# interfacez_r1.net
KiCad netlist of a schematic drawn in EAGLE
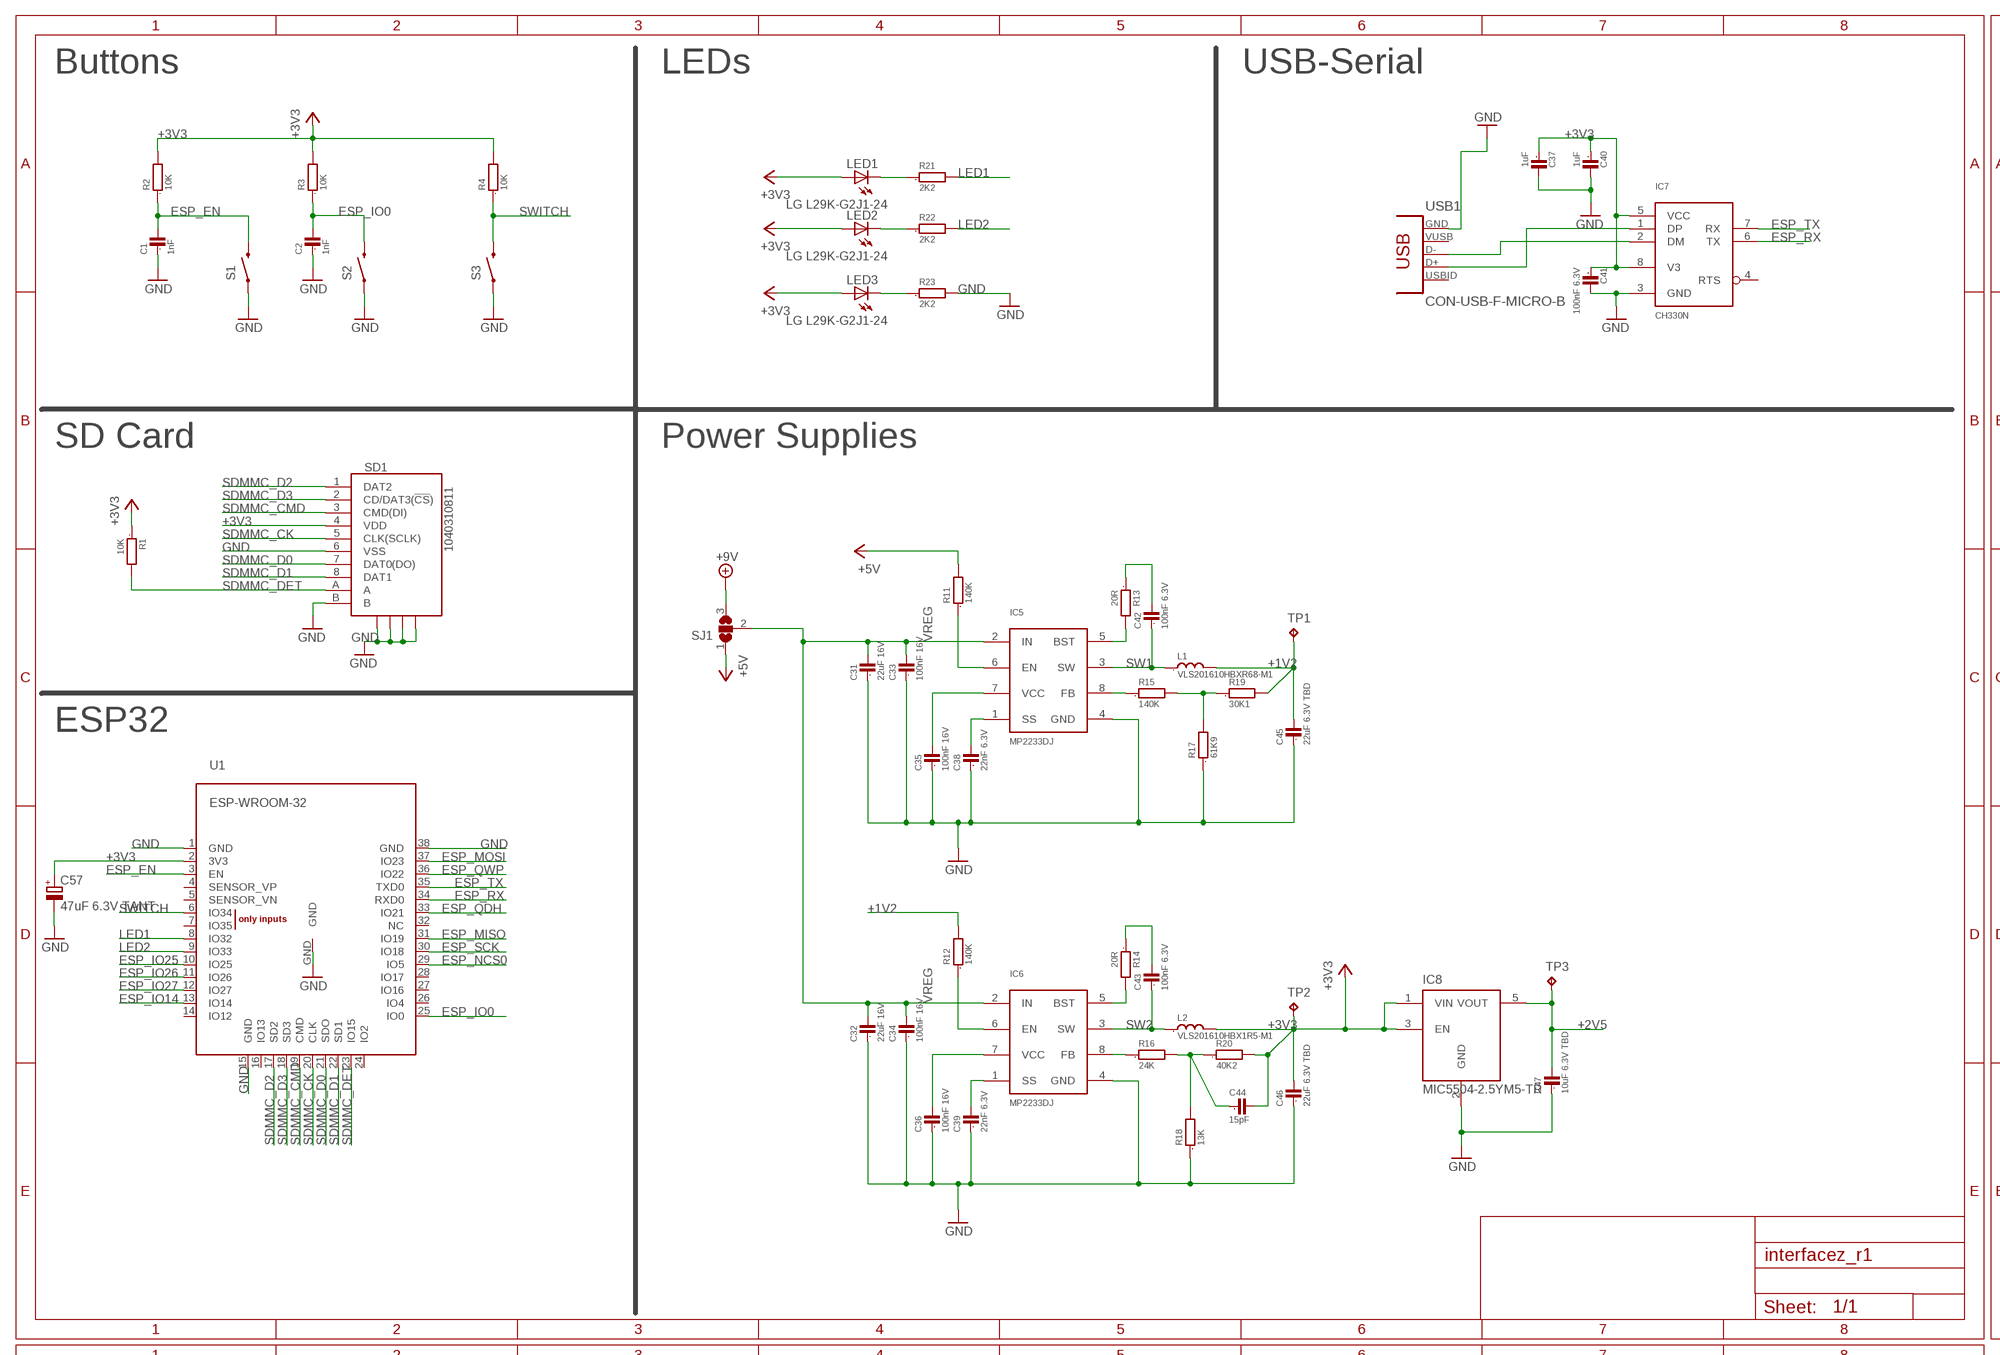
[diagram p0: schematic, sheet 1, part 1 of 3]
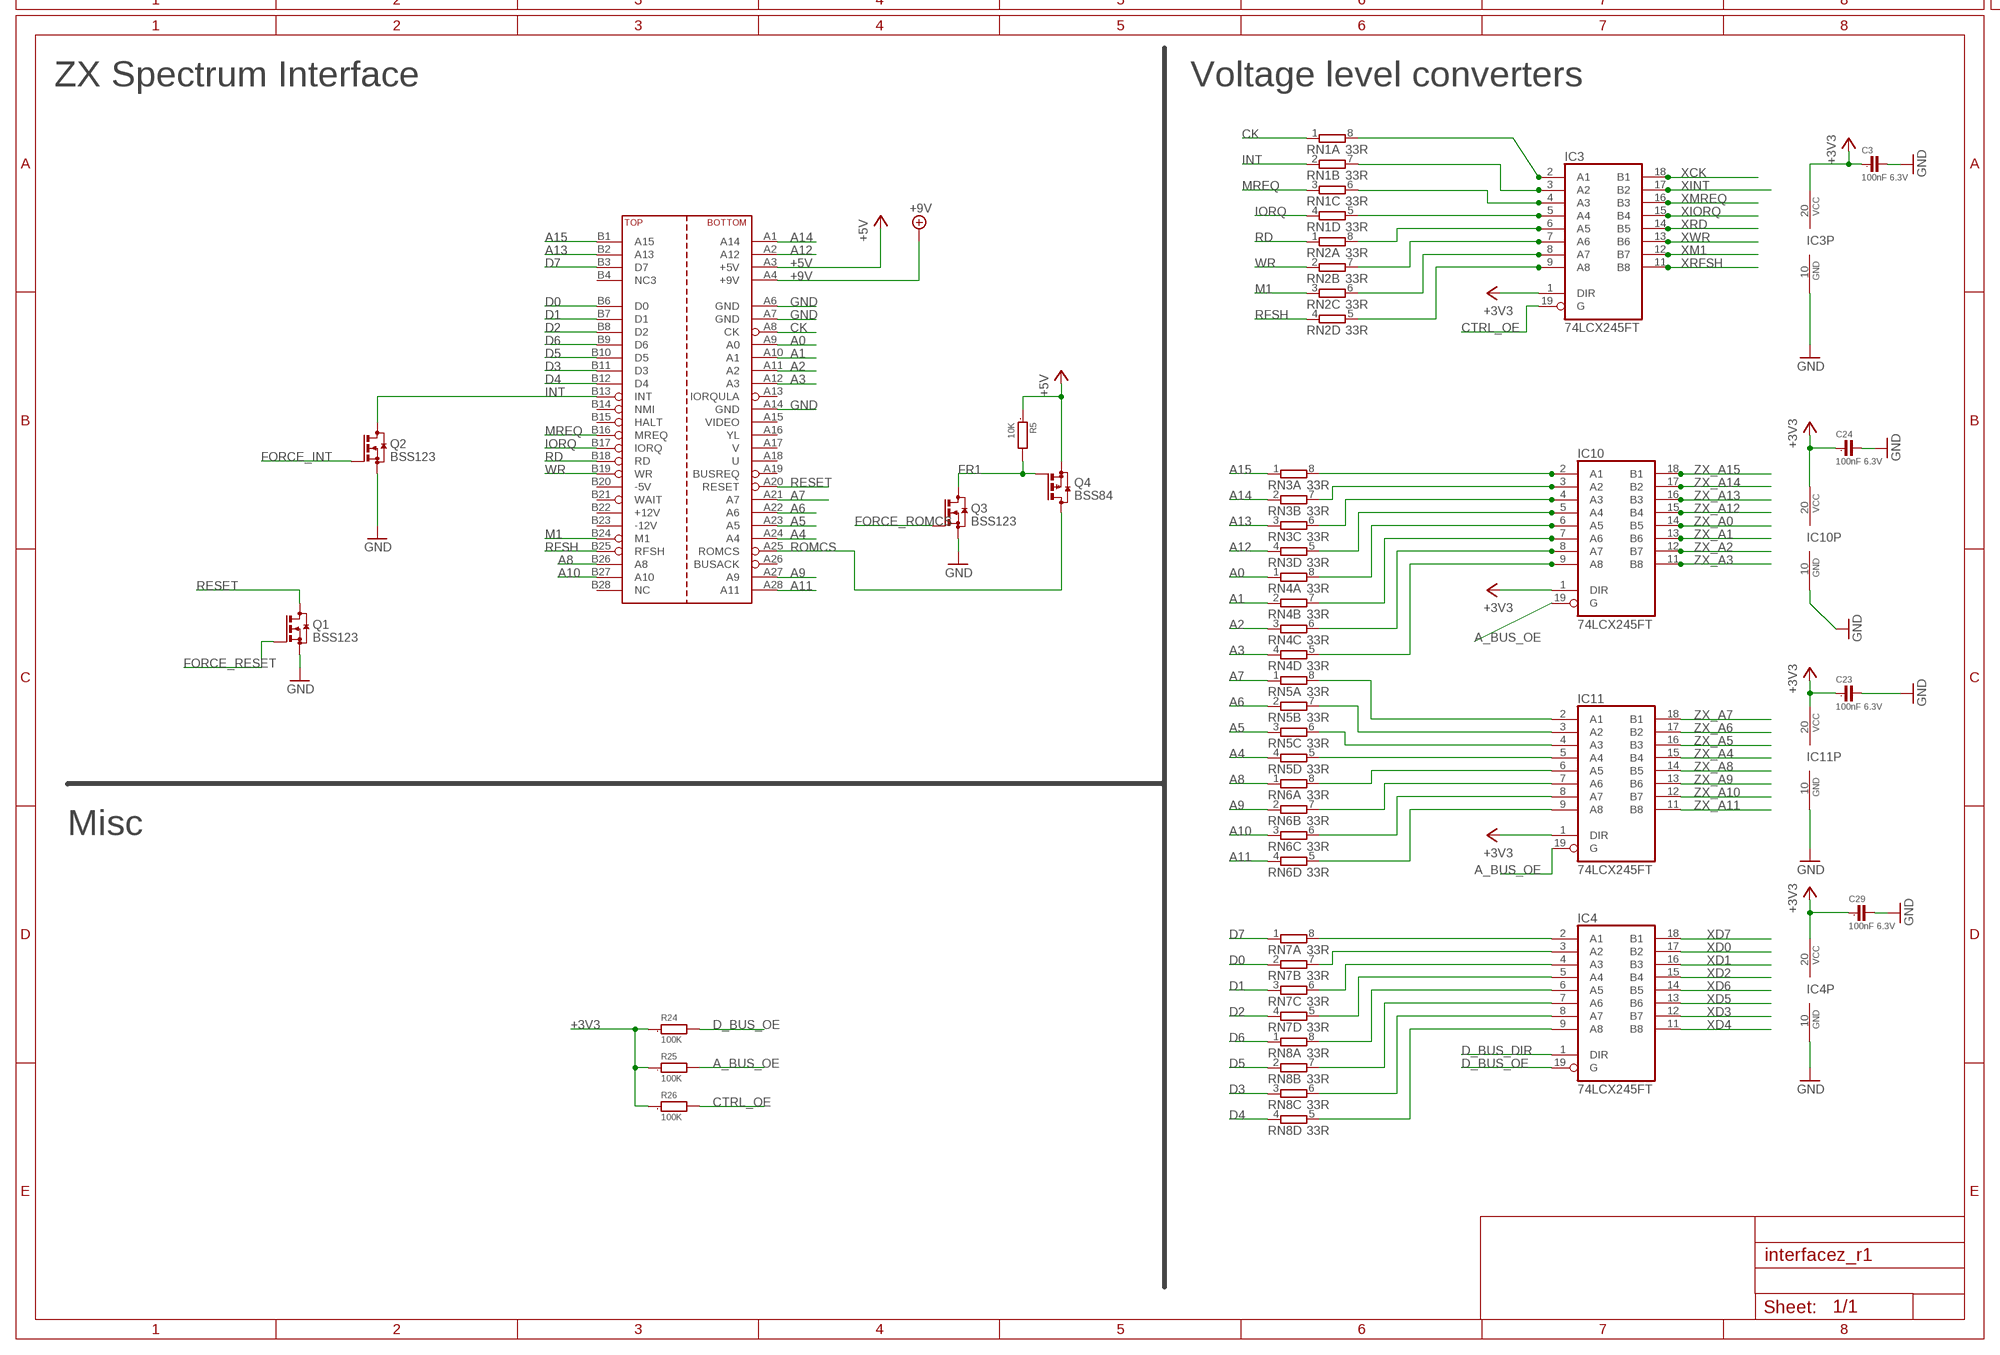
[diagram p1: schematic, sheet 1, part 2 of 3]
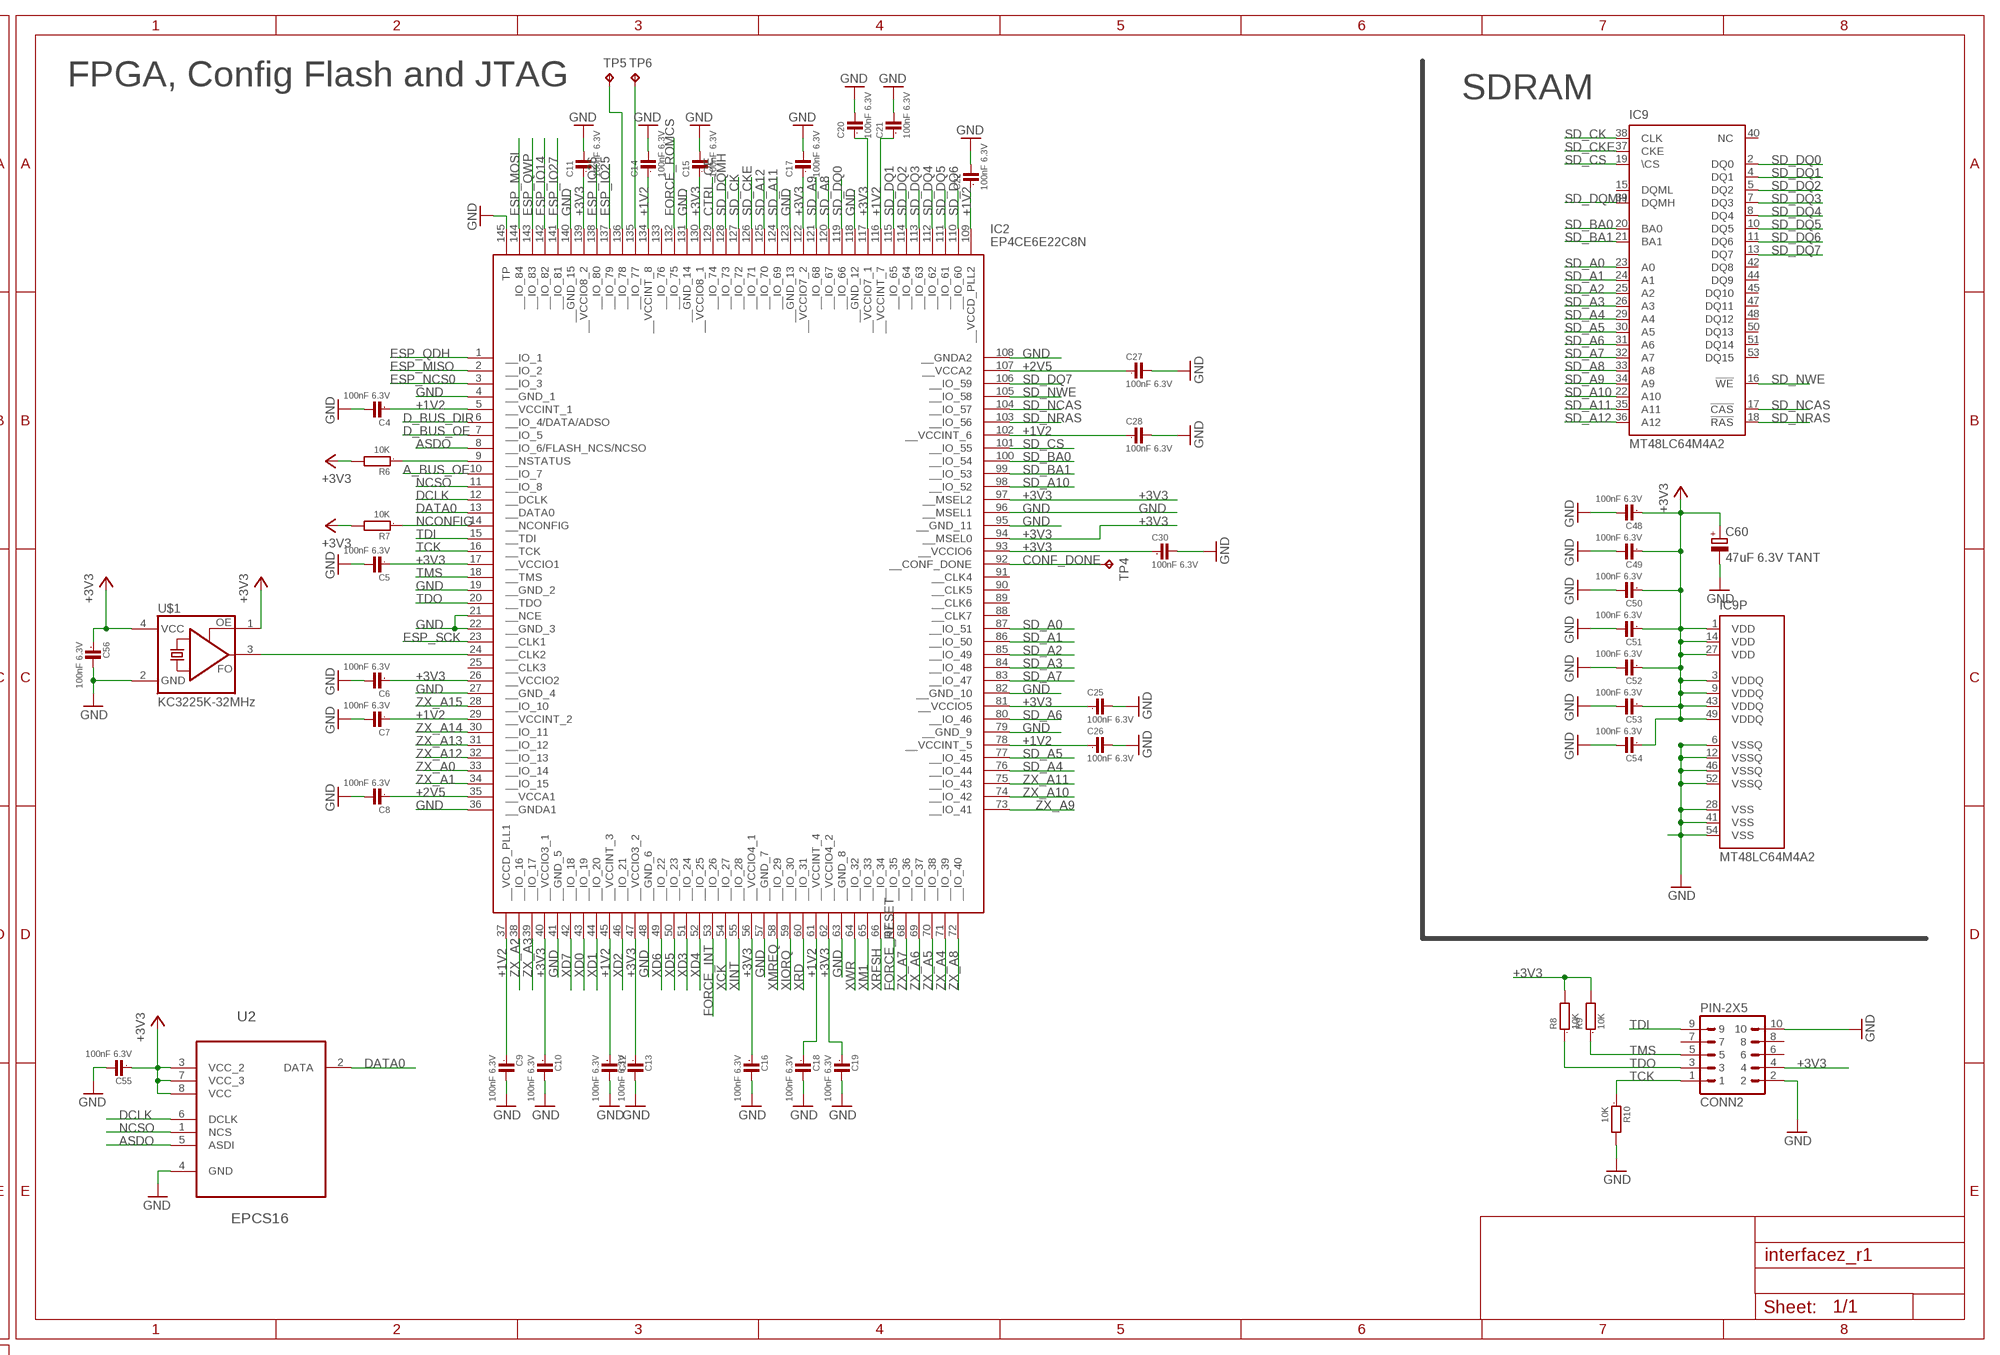
[diagram p2: schematic, sheet 1, part 3 of 3]

(export (version "E")
  (design (tool "Eeschema 10.0.6"))
  (components
    (comp (ref "C1")
      (value "1nF")
      (footprint "eagle-import:0603")
      (libsource (lib "eagle-import") (part "C0603"))
    )
    (comp (ref "C2")
      (value "1nF")
      (footprint "eagle-import:0603")
      (libsource (lib "eagle-import") (part "C0603"))
    )
    (comp (ref "C3")
      (value "100nF 6.3V")
      (footprint "eagle-import:0603")
      (libsource (lib "eagle-import") (part "C0603"))
    )
    (comp (ref "C4")
      (value "100nF 6.3V")
      (footprint "eagle-import:0603")
      (libsource (lib "eagle-import") (part "C0603"))
    )
    (comp (ref "C5")
      (value "100nF 6.3V")
      (footprint "eagle-import:0603")
      (libsource (lib "eagle-import") (part "C0603"))
    )
    (comp (ref "C6")
      (value "100nF 6.3V")
      (footprint "eagle-import:0603")
      (libsource (lib "eagle-import") (part "C0603"))
    )
    (comp (ref "C7")
      (value "100nF 6.3V")
      (footprint "eagle-import:0603")
      (libsource (lib "eagle-import") (part "C0603"))
    )
    (comp (ref "C8")
      (value "100nF 6.3V")
      (footprint "eagle-import:0603")
      (libsource (lib "eagle-import") (part "C0603"))
    )
    (comp (ref "C9")
      (value "100nF 6.3V")
      (footprint "eagle-import:0603")
      (libsource (lib "eagle-import") (part "C0603"))
    )
    (comp (ref "C10")
      (value "100nF 6.3V")
      (footprint "eagle-import:0603")
      (libsource (lib "eagle-import") (part "C0603"))
    )
    (comp (ref "C11")
      (value "100nF 6.3V")
      (footprint "eagle-import:0603")
      (libsource (lib "eagle-import") (part "C0603"))
    )
    (comp (ref "C12")
      (value "100nF 6.3V")
      (footprint "eagle-import:0603")
      (libsource (lib "eagle-import") (part "C0603"))
    )
    (comp (ref "C13")
      (value "100nF 6.3V")
      (footprint "eagle-import:0603")
      (libsource (lib "eagle-import") (part "C0603"))
    )
    (comp (ref "C14")
      (value "100nF 6.3V")
      (footprint "eagle-import:0603")
      (libsource (lib "eagle-import") (part "C0603"))
    )
    (comp (ref "C15")
      (value "100nF 6.3V")
      (footprint "eagle-import:0603")
      (libsource (lib "eagle-import") (part "C0603"))
    )
    (comp (ref "C16")
      (value "100nF 6.3V")
      (footprint "eagle-import:0603")
      (libsource (lib "eagle-import") (part "C0603"))
    )
    (comp (ref "C17")
      (value "100nF 6.3V")
      (footprint "eagle-import:0603")
      (libsource (lib "eagle-import") (part "C0603"))
    )
    (comp (ref "C18")
      (value "100nF 6.3V")
      (footprint "eagle-import:0603")
      (libsource (lib "eagle-import") (part "C0603"))
    )
    (comp (ref "C19")
      (value "100nF 6.3V")
      (footprint "eagle-import:0603")
      (libsource (lib "eagle-import") (part "C0603"))
    )
    (comp (ref "C20")
      (value "100nF 6.3V")
      (footprint "eagle-import:0603")
      (libsource (lib "eagle-import") (part "C0603"))
    )
    (comp (ref "C21")
      (value "100nF 6.3V")
      (footprint "eagle-import:0603")
      (libsource (lib "eagle-import") (part "C0603"))
    )
    (comp (ref "C22")
      (value "100nF 6.3V")
      (footprint "eagle-import:0603")
      (libsource (lib "eagle-import") (part "C0603"))
    )
    (comp (ref "C23")
      (value "100nF 6.3V")
      (footprint "eagle-import:0603")
      (libsource (lib "eagle-import") (part "C0603"))
    )
    (comp (ref "C24")
      (value "100nF 6.3V")
      (footprint "eagle-import:0603")
      (libsource (lib "eagle-import") (part "C0603"))
    )
    (comp (ref "C25")
      (value "100nF 6.3V")
      (footprint "eagle-import:0603")
      (libsource (lib "eagle-import") (part "C0603"))
    )
    (comp (ref "C26")
      (value "100nF 6.3V")
      (footprint "eagle-import:0603")
      (libsource (lib "eagle-import") (part "C0603"))
    )
    (comp (ref "C27")
      (value "100nF 6.3V")
      (footprint "eagle-import:0603")
      (libsource (lib "eagle-import") (part "C0603"))
    )
    (comp (ref "C28")
      (value "100nF 6.3V")
      (footprint "eagle-import:0603")
      (libsource (lib "eagle-import") (part "C0603"))
    )
    (comp (ref "C29")
      (value "100nF 6.3V")
      (footprint "eagle-import:0603")
      (libsource (lib "eagle-import") (part "C0603"))
    )
    (comp (ref "C30")
      (value "100nF 6.3V")
      (footprint "eagle-import:0603")
      (libsource (lib "eagle-import") (part "C0603"))
    )
    (comp (ref "C31")
      (value "22uF 16V")
      (footprint "eagle-import:1210")
      (libsource (lib "eagle-import") (part "C1210"))
    )
    (comp (ref "C32")
      (value "22uF 16V")
      (footprint "eagle-import:1210")
      (libsource (lib "eagle-import") (part "C1210"))
    )
    (comp (ref "C33")
      (value "100nF 16V")
      (footprint "eagle-import:0603")
      (libsource (lib "eagle-import") (part "C0603"))
    )
    (comp (ref "C34")
      (value "100nF 16V")
      (footprint "eagle-import:0603")
      (libsource (lib "eagle-import") (part "C0603"))
    )
    (comp (ref "C35")
      (value "100nF 16V")
      (footprint "eagle-import:0603")
      (libsource (lib "eagle-import") (part "C0603"))
    )
    (comp (ref "C36")
      (value "100nF 16V")
      (footprint "eagle-import:0603")
      (libsource (lib "eagle-import") (part "C0603"))
    )
    (comp (ref "C37")
      (value "1uF")
      (footprint "eagle-import:0603")
      (libsource (lib "eagle-import") (part "C0603"))
    )
    (comp (ref "C38")
      (value "22nF 6.3V")
      (footprint "eagle-import:0603")
      (libsource (lib "eagle-import") (part "C0603"))
    )
    (comp (ref "C39")
      (value "22nF 6.3V")
      (footprint "eagle-import:0603")
      (libsource (lib "eagle-import") (part "C0603"))
    )
    (comp (ref "C40")
      (value "1uF")
      (footprint "eagle-import:0603")
      (libsource (lib "eagle-import") (part "C0603"))
    )
    (comp (ref "C41")
      (value "100nF 6.3V")
      (footprint "eagle-import:0603")
      (libsource (lib "eagle-import") (part "C0603"))
    )
    (comp (ref "C42")
      (value "100nF 6.3V")
      (footprint "eagle-import:0603")
      (libsource (lib "eagle-import") (part "C0603"))
    )
    (comp (ref "C43")
      (value "100nF 6.3V")
      (footprint "eagle-import:0603")
      (libsource (lib "eagle-import") (part "C0603"))
    )
    (comp (ref "C44")
      (value "15pF")
      (footprint "eagle-import:0603")
      (libsource (lib "eagle-import") (part "C0603"))
    )
    (comp (ref "C45")
      (value "22uF 6.3V TBD")
      (footprint "eagle-import:0805")
      (libsource (lib "eagle-import") (part "C0805"))
    )
    (comp (ref "C46")
      (value "22uF 6.3V TBD")
      (footprint "eagle-import:0805")
      (libsource (lib "eagle-import") (part "C0805"))
    )
    (comp (ref "C47")
      (value "10uF 6.3V TBD")
      (footprint "eagle-import:0805")
      (libsource (lib "eagle-import") (part "C0805"))
    )
    (comp (ref "C48")
      (value "100nF 6.3V")
      (footprint "eagle-import:0603")
      (libsource (lib "eagle-import") (part "C0603"))
    )
    (comp (ref "C49")
      (value "100nF 6.3V")
      (footprint "eagle-import:0603")
      (libsource (lib "eagle-import") (part "C0603"))
    )
    (comp (ref "C50")
      (value "100nF 6.3V")
      (footprint "eagle-import:0603")
      (libsource (lib "eagle-import") (part "C0603"))
    )
    (comp (ref "C51")
      (value "100nF 6.3V")
      (footprint "eagle-import:0603")
      (libsource (lib "eagle-import") (part "C0603"))
    )
    (comp (ref "C52")
      (value "100nF 6.3V")
      (footprint "eagle-import:0603")
      (libsource (lib "eagle-import") (part "C0603"))
    )
    (comp (ref "C53")
      (value "100nF 6.3V")
      (footprint "eagle-import:0603")
      (libsource (lib "eagle-import") (part "C0603"))
    )
    (comp (ref "C54")
      (value "100nF 6.3V")
      (footprint "eagle-import:0603")
      (libsource (lib "eagle-import") (part "C0603"))
    )
    (comp (ref "C55")
      (value "100nF 6.3V")
      (footprint "eagle-import:0603")
      (libsource (lib "eagle-import") (part "C0603"))
    )
    (comp (ref "C56")
      (value "100nF 6.3V")
      (footprint "eagle-import:0603")
      (libsource (lib "eagle-import") (part "C0603"))
    )
    (comp (ref "C57")
      (value "47uF 6.3V TANT")
      (footprint "eagle-import:TANT_CASE_A")
      (libsource (lib "eagle-import") (part "TANT_CASE_A"))
    )
    (comp (ref "C60")
      (value "47uF 6.3V TANT")
      (footprint "eagle-import:TANT_CASE_A")
      (libsource (lib "eagle-import") (part "TANT_CASE_A"))
    )
    (comp (ref "CONN1")
      (value "ZX_EDGE_DAUGHTERBOARD")
      (footprint "eagle-import:ZX-EDGE-DAUGHTERBOARD")
      (libsource (lib "eagle-import") (part "ZX_EDGE_DAUGHTERBOARD"))
    )
    (comp (ref "CONN2")
      (value "PIN-2X5")
      (footprint "eagle-import:PIN-2X5")
      (libsource (lib "eagle-import") (part "PIN-2X5"))
    )
    (comp (ref "IC2")
      (value "EP4CE6E22C8N")
      (footprint "eagle-import:QFP50P2200X2200X165-145N")
      (fields (field (name "MOUSER_PART_NUMBER") "989-EP4CE6E22C8N"))
      (libsource (lib "eagle-import") (part "EP4CE6E22C8N"))
    )
    (comp (ref "IC3")
      (value "74LCX245FT")
      (footprint "eagle-import:TSSOP20")
      (libsource (lib "eagle-import") (part "74245"))
    )
    (comp (ref "IC4")
      (value "74LCX245FT")
      (footprint "eagle-import:TSSOP20")
      (libsource (lib "eagle-import") (part "74245"))
    )
    (comp (ref "IC5")
      (value "MP2233DJ")
      (footprint "eagle-import:SOT23-8L")
      (libsource (lib "eagle-import") (part "MP2233DJ"))
    )
    (comp (ref "IC6")
      (value "MP2233DJ")
      (footprint "eagle-import:SOT23-8L")
      (libsource (lib "eagle-import") (part "MP2233DJ"))
    )
    (comp (ref "IC7")
      (value "CH330N")
      (footprint "eagle-import:SOIC8")
      (libsource (lib "eagle-import") (part "CH330N"))
    )
    (comp (ref "IC8")
      (value "MIC5504-2.5YM5-TR")
      (footprint "eagle-import:SOT23-5L")
      (libsource (lib "eagle-import") (part "MIC550X"))
    )
    (comp (ref "IC9")
      (value "MT48LC64M4A2")
      (footprint "eagle-import:TSOP54-400")
      (libsource (lib "eagle-import") (part "MT48LC64M4A2"))
    )
    (comp (ref "IC10")
      (value "74LCX245FT")
      (footprint "eagle-import:TSSOP20")
      (libsource (lib "eagle-import") (part "74245"))
    )
    (comp (ref "IC11")
      (value "74LCX245FT")
      (footprint "eagle-import:TSSOP20")
      (libsource (lib "eagle-import") (part "74245"))
    )
    (comp (ref "L1")
      (value "VLS201610HBXR68-M1")
      (footprint "eagle-import:IND_0806")
      (libsource (lib "eagle-import") (part "VLS201610HBXR68-M1"))
    )
    (comp (ref "L2")
      (value "VLS201610HBX1R5-M1")
      (footprint "eagle-import:IND_0806")
      (libsource (lib "eagle-import") (part "VLS201610HBX1R5-M1"))
    )
    (comp (ref "LED1")
      (value "LG L29K-G2J1-24")
      (footprint "eagle-import:LED-603")
      (libsource (lib "eagle-import") (part "LED-0603"))
    )
    (comp (ref "LED2")
      (value "LG L29K-G2J1-24")
      (footprint "eagle-import:LED-603")
      (libsource (lib "eagle-import") (part "LED-0603"))
    )
    (comp (ref "LED3")
      (value "LG L29K-G2J1-24")
      (footprint "eagle-import:LED-603")
      (libsource (lib "eagle-import") (part "LED-0603"))
    )
    (comp (ref "Q1")
      (value "BSS123")
      (footprint "eagle-import:SOT23")
      (libsource (lib "eagle-import") (part "BSS123"))
    )
    (comp (ref "Q2")
      (value "BSS123")
      (footprint "eagle-import:SOT23")
      (libsource (lib "eagle-import") (part "BSS123"))
    )
    (comp (ref "Q3")
      (value "BSS123")
      (footprint "eagle-import:SOT23")
      (libsource (lib "eagle-import") (part "BSS123"))
    )
    (comp (ref "Q4")
      (value "BSS84")
      (footprint "eagle-import:SOT23")
      (libsource (lib "eagle-import") (part "BSS84"))
    )
    (comp (ref "R1")
      (value "10K")
      (footprint "eagle-import:0603")
      (libsource (lib "eagle-import") (part "R0603"))
    )
    (comp (ref "R2")
      (value "10K")
      (footprint "eagle-import:0603")
      (libsource (lib "eagle-import") (part "R0603"))
    )
    (comp (ref "R3")
      (value "10K")
      (footprint "eagle-import:0603")
      (libsource (lib "eagle-import") (part "R0603"))
    )
    (comp (ref "R4")
      (value "10K")
      (footprint "eagle-import:0603")
      (libsource (lib "eagle-import") (part "R0603"))
    )
    (comp (ref "R5")
      (value "10K")
      (footprint "eagle-import:0603")
      (libsource (lib "eagle-import") (part "R0603"))
    )
    (comp (ref "R6")
      (value "10K")
      (footprint "eagle-import:0603")
      (libsource (lib "eagle-import") (part "R0603"))
    )
    (comp (ref "R7")
      (value "10K")
      (footprint "eagle-import:0603")
      (libsource (lib "eagle-import") (part "R0603"))
    )
    (comp (ref "R8")
      (value "10K")
      (footprint "eagle-import:0603")
      (libsource (lib "eagle-import") (part "R0603"))
    )
    (comp (ref "R9")
      (value "10K")
      (footprint "eagle-import:0603")
      (libsource (lib "eagle-import") (part "R0603"))
    )
    (comp (ref "R10")
      (value "10K")
      (footprint "eagle-import:0603")
      (libsource (lib "eagle-import") (part "R0603"))
    )
    (comp (ref "R11")
      (value "140K")
      (footprint "eagle-import:0603")
      (libsource (lib "eagle-import") (part "R0603"))
    )
    (comp (ref "R12")
      (value "140K")
      (footprint "eagle-import:0603")
      (libsource (lib "eagle-import") (part "R0603"))
    )
    (comp (ref "R13")
      (value "20R")
      (footprint "eagle-import:0603")
      (libsource (lib "eagle-import") (part "R0603"))
    )
    (comp (ref "R14")
      (value "20R")
      (footprint "eagle-import:0603")
      (libsource (lib "eagle-import") (part "R0603"))
    )
    (comp (ref "R15")
      (value "140K")
      (footprint "eagle-import:0603")
      (libsource (lib "eagle-import") (part "R0603"))
    )
    (comp (ref "R16")
      (value "24K")
      (footprint "eagle-import:0603")
      (libsource (lib "eagle-import") (part "R0603"))
    )
    (comp (ref "R17")
      (value "61K9")
      (footprint "eagle-import:0603")
      (libsource (lib "eagle-import") (part "R0603"))
    )
    (comp (ref "R18")
      (value "13K")
      (footprint "eagle-import:0603")
      (libsource (lib "eagle-import") (part "R0603"))
    )
    (comp (ref "R19")
      (value "30K1")
      (footprint "eagle-import:0603")
      (libsource (lib "eagle-import") (part "R0603"))
    )
    (comp (ref "R20")
      (value "40K2")
      (footprint "eagle-import:0603")
      (libsource (lib "eagle-import") (part "R0603"))
    )
    (comp (ref "R21")
      (value "2K2")
      (footprint "eagle-import:0603")
      (libsource (lib "eagle-import") (part "R0603"))
    )
    (comp (ref "R22")
      (value "2K2")
      (footprint "eagle-import:0603")
      (libsource (lib "eagle-import") (part "R0603"))
    )
    (comp (ref "R23")
      (value "2K2")
      (footprint "eagle-import:0603")
      (libsource (lib "eagle-import") (part "R0603"))
    )
    (comp (ref "R24")
      (value "100K")
      (footprint "eagle-import:0603")
      (libsource (lib "eagle-import") (part "R0603"))
    )
    (comp (ref "R25")
      (value "100K")
      (footprint "eagle-import:0603")
      (libsource (lib "eagle-import") (part "R0603"))
    )
    (comp (ref "R26")
      (value "100K")
      (footprint "eagle-import:0603")
      (libsource (lib "eagle-import") (part "R0603"))
    )
    (comp (ref "RN1")
      (value "33R")
      (footprint "eagle-import:EXB28V")
      (libsource (lib "eagle-import") (part "4R-NEXB28V"))
    )
    (comp (ref "RN2")
      (value "33R")
      (footprint "eagle-import:EXB28V")
      (libsource (lib "eagle-import") (part "4R-NEXB28V"))
    )
    (comp (ref "RN3")
      (value "33R")
      (footprint "eagle-import:EXB28V")
      (libsource (lib "eagle-import") (part "4R-NEXB28V"))
    )
    (comp (ref "RN4")
      (value "33R")
      (footprint "eagle-import:EXB28V")
      (libsource (lib "eagle-import") (part "4R-NEXB28V"))
    )
    (comp (ref "RN5")
      (value "33R")
      (footprint "eagle-import:EXB28V")
      (libsource (lib "eagle-import") (part "4R-NEXB28V"))
    )
    (comp (ref "RN6")
      (value "33R")
      (footprint "eagle-import:EXB28V")
      (libsource (lib "eagle-import") (part "4R-NEXB28V"))
    )
    (comp (ref "RN7")
      (value "33R")
      (footprint "eagle-import:EXB28V")
      (libsource (lib "eagle-import") (part "4R-NEXB28V"))
    )
    (comp (ref "RN8")
      (value "33R")
      (footprint "eagle-import:EXB28V")
      (libsource (lib "eagle-import") (part "4R-NEXB28V"))
    )
    (comp (ref "S1")
      (value "SWITCHES_SMD-4")
      (footprint "eagle-import:TACTILE_SWITCH_TALL")
      (libsource (lib "eagle-import") (part "SWITCHES_SMD-4"))
    )
    (comp (ref "S2")
      (value "SWITCHES_SMD-4")
      (footprint "eagle-import:TACTILE_SWITCH_TALL")
      (libsource (lib "eagle-import") (part "SWITCHES_SMD-4"))
    )
    (comp (ref "S3")
      (value "SWITCHES_SMD-4")
      (footprint "eagle-import:TACTILE_SWITCH_TALL")
      (libsource (lib "eagle-import") (part "SWITCHES_SMD-4"))
    )
    (comp (ref "SD1")
      (value "1040310811")
      (footprint "eagle-import:1040310811")
      (libsource (lib "eagle-import") (part "1040310811"))
    )
    (comp (ref "SJ1")
      (value "SJ2W")
      (footprint "eagle-import:SJ_2")
      (libsource (lib "eagle-import") (part "SJ2W"))
    )
    (comp (ref "TP1")
      (value "TPTP12R")
      (footprint "eagle-import:TP12R")
      (libsource (lib "eagle-import") (part "TPTP12R"))
    )
    (comp (ref "TP2")
      (value "TPTP12R")
      (footprint "eagle-import:TP12R")
      (libsource (lib "eagle-import") (part "TPTP12R"))
    )
    (comp (ref "TP3")
      (value "TPTP12R")
      (footprint "eagle-import:TP12R")
      (libsource (lib "eagle-import") (part "TPTP12R"))
    )
    (comp (ref "TP4")
      (value "TPTP08R")
      (footprint "eagle-import:TP08R")
      (libsource (lib "eagle-import") (part "TPTP08R"))
    )
    (comp (ref "TP5")
      (value "TPTP12R")
      (footprint "eagle-import:TP12R")
      (libsource (lib "eagle-import") (part "TPTP12R"))
    )
    (comp (ref "TP6")
      (value "TPTP12R")
      (footprint "eagle-import:TP12R")
      (libsource (lib "eagle-import") (part "TPTP12R"))
    )
    (comp (ref "U$1")
      (value "KC3225K-32MHz")
      (footprint "eagle-import:KC3225K")
      (libsource (lib "eagle-import") (part "KC3225K"))
    )
    (comp (ref "U1")
      (value "ESP-WROOM-32")
      (footprint "eagle-import:ESP-WROOM-32")
      (libsource (lib "eagle-import") (part "ESP-WROOM-32"))
    )
    (comp (ref "U2")
      (value "EPCS16")
      (footprint "eagle-import:SOIC127P600X175-8N")
      (fields (field (name "MPN") "EPCS1SI8N"))
      (libsource (lib "eagle-import") (part "EPCS1SI8N"))
    )
    (comp (ref "USB1")
      (value "CON-USB-F-MICRO-B")
      (footprint "eagle-import:CONN_USB_MICRO-B")
      (libsource (lib "eagle-import") (part "CON-USB-F-MICRO-B"))
    )
  )
  (nets
    (net (code "1") (name "+3V3") (class "Default")
      (node (ref "C10") (pin "1") (pinfunction "1_1") (pintype "passive"))
      (node (ref "C11") (pin "1") (pinfunction "1_1") (pintype "passive"))
      (node (ref "C13") (pin "1") (pinfunction "1_1") (pintype "passive"))
      (node (ref "C15") (pin "1") (pinfunction "1_1") (pintype "passive"))
      (node (ref "C16") (pin "1") (pinfunction "1_1") (pintype "passive"))
      (node (ref "C17") (pin "1") (pinfunction "1_1") (pintype "passive"))
      (node (ref "C19") (pin "1") (pinfunction "1_1") (pintype "passive"))
      (node (ref "C20") (pin "1") (pinfunction "1_1") (pintype "passive"))
      (node (ref "C23") (pin "1") (pinfunction "1_1") (pintype "passive"))
      (node (ref "C24") (pin "1") (pinfunction "1_1") (pintype "passive"))
      (node (ref "C25") (pin "1") (pinfunction "1_1") (pintype "passive"))
      (node (ref "C29") (pin "1") (pinfunction "1_1") (pintype "passive"))
      (node (ref "C3") (pin "1") (pinfunction "1_1") (pintype "passive"))
      (node (ref "C30") (pin "1") (pinfunction "1_1") (pintype "passive"))
      (node (ref "C37") (pin "1") (pinfunction "1_1") (pintype "passive"))
      (node (ref "C40") (pin "1") (pinfunction "1_1") (pintype "passive"))
      (node (ref "C41") (pin "1") (pinfunction "1_1") (pintype "passive"))
      (node (ref "C44") (pin "2") (pinfunction "2_2") (pintype "passive"))
      (node (ref "C46") (pin "2") (pinfunction "2_2") (pintype "passive"))
      (node (ref "C48") (pin "1") (pinfunction "1_1") (pintype "passive"))
      (node (ref "C49") (pin "1") (pinfunction "1_1") (pintype "passive"))
      (node (ref "C5") (pin "1") (pinfunction "1_1") (pintype "passive"))
      (node (ref "C50") (pin "1") (pinfunction "1_1") (pintype "passive"))
      (node (ref "C51") (pin "1") (pinfunction "1_1") (pintype "passive"))
      (node (ref "C52") (pin "1") (pinfunction "1_1") (pintype "passive"))
      (node (ref "C53") (pin "1") (pinfunction "1_1") (pintype "passive"))
      (node (ref "C54") (pin "1") (pinfunction "1_1") (pintype "passive"))
      (node (ref "C55") (pin "1") (pinfunction "1_1") (pintype "passive"))
      (node (ref "C56") (pin "1") (pinfunction "1_1") (pintype "passive"))
      (node (ref "C57") (pin "PLUS") (pinfunction "+_PLUS") (pintype "passive"))
      (node (ref "C6") (pin "1") (pinfunction "1_1") (pintype "passive"))
      (node (ref "C60") (pin "PLUS") (pinfunction "+_PLUS") (pintype "passive"))
      (node (ref "CONN2") (pin "4") (pinfunction "4_4") (pintype "passive"))
      (node (ref "IC10") (pin "1") (pinfunction "DIR_1") (pintype "input"))
      (node (ref "IC10") (pin "20") (pinfunction "VCC_20") (pintype "power_in"))
      (node (ref "IC11") (pin "1") (pinfunction "DIR_1") (pintype "input"))
      (node (ref "IC11") (pin "20") (pinfunction "VCC_20") (pintype "power_in"))
      (node (ref "IC2") (pin "117") (pinfunction "__VCCIO7_1_117") (pintype "power_in"))
      (node (ref "IC2") (pin "122") (pinfunction "__VCCIO7_2_122") (pintype "power_in"))
      (node (ref "IC2") (pin "130") (pinfunction "__VCCIO8_1_130") (pintype "power_in"))
      (node (ref "IC2") (pin "139") (pinfunction "__VCCIO8_2_139") (pintype "power_in"))
      (node (ref "IC2") (pin "17") (pinfunction "__VCCIO1_17") (pintype "power_in"))
      (node (ref "IC2") (pin "26") (pinfunction "__VCCIO2_26") (pintype "power_in"))
      (node (ref "IC2") (pin "40") (pinfunction "__VCCIO3_1_40") (pintype "power_in"))
      (node (ref "IC2") (pin "47") (pinfunction "__VCCIO3_2_47") (pintype "power_in"))
      (node (ref "IC2") (pin "56") (pinfunction "__VCCIO4_1_56") (pintype "power_in"))
      (node (ref "IC2") (pin "62") (pinfunction "__VCCIO4_2_62") (pintype "power_in"))
      (node (ref "IC2") (pin "81") (pinfunction "__VCCIO5_81") (pintype "power_in"))
      (node (ref "IC2") (pin "93") (pinfunction "__VCCIO6_93") (pintype "power_in"))
      (node (ref "IC2") (pin "94") (pinfunction "__MSEL0_94") (pintype "bidirectional"))
      (node (ref "IC2") (pin "97") (pinfunction "__MSEL2_97") (pintype "bidirectional"))
      (node (ref "IC3") (pin "1") (pinfunction "DIR_1") (pintype "input"))
      (node (ref "IC3") (pin "20") (pinfunction "VCC_20") (pintype "power_in"))
      (node (ref "IC4") (pin "20") (pinfunction "VCC_20") (pintype "power_in"))
      (node (ref "IC7") (pin "5") (pinfunction "VCC_5") (pintype "power_in"))
      (node (ref "IC7") (pin "8") (pinfunction "V3_8") (pintype "passive"))
      (node (ref "IC8") (pin "1") (pinfunction "VIN_1") (pintype "power_in"))
      (node (ref "IC8") (pin "3") (pinfunction "EN_3") (pintype "input"))
      (node (ref "IC9") (pin "1") (pinfunction "VDD_1") (pintype "power_in"))
      (node (ref "IC9") (pin "14") (pinfunction "VDD_14") (pintype "power_in"))
      (node (ref "IC9") (pin "27") (pinfunction "VDD_27") (pintype "power_in"))
      (node (ref "IC9") (pin "3") (pinfunction "VDDQ_3") (pintype "power_in"))
      (node (ref "IC9") (pin "43") (pinfunction "VDDQ_43") (pintype "power_in"))
      (node (ref "IC9") (pin "49") (pinfunction "VDDQ_49") (pintype "power_in"))
      (node (ref "IC9") (pin "9") (pinfunction "VDDQ_9") (pintype "power_in"))
      (node (ref "L2") (pin "P$2") (pinfunction "2_P$2") (pintype "passive"))
      (node (ref "LED1") (pin "A") (pinfunction "A_A") (pintype "passive"))
      (node (ref "LED2") (pin "A") (pinfunction "A_A") (pintype "passive"))
      (node (ref "LED3") (pin "A") (pinfunction "A_A") (pintype "passive"))
      (node (ref "R1") (pin "1") (pinfunction "1_1") (pintype "passive"))
      (node (ref "R2") (pin "2") (pinfunction "2_2") (pintype "passive"))
      (node (ref "R20") (pin "2") (pinfunction "2_2") (pintype "passive"))
      (node (ref "R24") (pin "1") (pinfunction "1_1") (pintype "passive"))
      (node (ref "R25") (pin "1") (pinfunction "1_1") (pintype "passive"))
      (node (ref "R26") (pin "1") (pinfunction "1_1") (pintype "passive"))
      (node (ref "R3") (pin "2") (pinfunction "2_2") (pintype "passive"))
      (node (ref "R4") (pin "2") (pinfunction "2_2") (pintype "passive"))
      (node (ref "R6") (pin "2") (pinfunction "2_2") (pintype "passive"))
      (node (ref "R7") (pin "2") (pinfunction "2_2") (pintype "passive"))
      (node (ref "R8") (pin "2") (pinfunction "2_2") (pintype "passive"))
      (node (ref "R9") (pin "2") (pinfunction "2_2") (pintype "passive"))
      (node (ref "SD1") (pin "4") (pinfunction "VDD_4") (pintype "power_in"))
      (node (ref "TP2") (pin "TP") (pinfunction "TP_TP") (pintype "input"))
      (node (ref "U$1") (pin "1") (pinfunction "OE_1") (pintype "input"))
      (node (ref "U$1") (pin "4") (pinfunction "VCC_4") (pintype "power_in"))
      (node (ref "U1") (pin "2") (pinfunction "3V3_2") (pintype "bidirectional"))
      (node (ref "U2") (pin "3") (pinfunction "VCC_2_3") (pintype "power_in"))
      (node (ref "U2") (pin "7") (pinfunction "VCC_3_7") (pintype "power_in"))
      (node (ref "U2") (pin "8") (pinfunction "VCC_8") (pintype "power_in"))
    )
    (net (code "2") (name "+5V") (class "Default")
      (node (ref "CONN1") (pin "A3") (pinfunction "+5V_A3") (pintype "power_in"))
      (node (ref "Q4") (pin "2") (pinfunction "S_2") (pintype "passive"))
      (node (ref "R11") (pin "2") (pinfunction "2_2") (pintype "passive"))
      (node (ref "R5") (pin "1") (pinfunction "1_1") (pintype "passive"))
      (node (ref "SJ1") (pin "1") (pinfunction "1_1") (pintype "passive"))
    )
    (net (code "3") (name "+9V") (class "Default")
      (node (ref "CONN1") (pin "A4") (pinfunction "+9V_A4") (pintype "power_in"))
      (node (ref "SJ1") (pin "3") (pinfunction "3_3") (pintype "passive"))
    )
    (net (code "4") (name "/+1V2") (class "Default")
      (node (ref "C12") (pin "1") (pinfunction "1_1") (pintype "passive"))
      (node (ref "C14") (pin "1") (pinfunction "1_1") (pintype "passive"))
      (node (ref "C18") (pin "1") (pinfunction "1_1") (pintype "passive"))
      (node (ref "C21") (pin "1") (pinfunction "1_1") (pintype "passive"))
      (node (ref "C22") (pin "1") (pinfunction "1_1") (pintype "passive"))
      (node (ref "C26") (pin "1") (pinfunction "1_1") (pintype "passive"))
      (node (ref "C28") (pin "1") (pinfunction "1_1") (pintype "passive"))
      (node (ref "C4") (pin "1") (pinfunction "1_1") (pintype "passive"))
      (node (ref "C45") (pin "2") (pinfunction "2_2") (pintype "passive"))
      (node (ref "C7") (pin "1") (pinfunction "1_1") (pintype "passive"))
      (node (ref "C9") (pin "1") (pinfunction "1_1") (pintype "passive"))
      (node (ref "IC2") (pin "102") (pinfunction "__VCCINT_6_102") (pintype "power_in"))
      (node (ref "IC2") (pin "109") (pinfunction "__VCCD_PLL2_109") (pintype "power_in"))
      (node (ref "IC2") (pin "116") (pinfunction "__VCCINT_7_116") (pintype "power_in"))
      (node (ref "IC2") (pin "134") (pinfunction "__VCCINT_8_134") (pintype "power_in"))
      (node (ref "IC2") (pin "29") (pinfunction "__VCCINT_2_29") (pintype "power_in"))
      (node (ref "IC2") (pin "37") (pinfunction "__VCCD_PLL1_37") (pintype "power_in"))
      (node (ref "IC2") (pin "45") (pinfunction "__VCCINT_3_45") (pintype "power_in"))
      (node (ref "IC2") (pin "5") (pinfunction "__VCCINT_1_5") (pintype "power_in"))
      (node (ref "IC2") (pin "61") (pinfunction "__VCCINT_4_61") (pintype "power_in"))
      (node (ref "IC2") (pin "78") (pinfunction "__VCCINT_5_78") (pintype "power_in"))
      (node (ref "L1") (pin "P$2") (pinfunction "2_P$2") (pintype "passive"))
      (node (ref "R12") (pin "2") (pinfunction "2_2") (pintype "passive"))
      (node (ref "R19") (pin "2") (pinfunction "2_2") (pintype "passive"))
      (node (ref "TP1") (pin "TP") (pinfunction "TP_TP") (pintype "input"))
    )
    (net (code "5") (name "/+2V5") (class "Default")
      (node (ref "C27") (pin "1") (pinfunction "1_1") (pintype "passive"))
      (node (ref "C47") (pin "2") (pinfunction "2_2") (pintype "passive"))
      (node (ref "C8") (pin "1") (pinfunction "1_1") (pintype "passive"))
      (node (ref "IC2") (pin "107") (pinfunction "__VCCA2_107") (pintype "power_in"))
      (node (ref "IC2") (pin "35") (pinfunction "__VCCA1_35") (pintype "power_in"))
      (node (ref "IC8") (pin "5") (pinfunction "VOUT_5") (pintype "power_in"))
      (node (ref "TP3") (pin "TP") (pinfunction "TP_TP") (pintype "input"))
    )
    (net (code "6") (name "/+12V") (class "Default")
      (node (ref "CONN1") (pin "B22") (pinfunction "+12V_B22") (pintype "power_in"))
    )
    (net (code "7") (name "/-5V") (class "Default")
      (node (ref "CONN1") (pin "B20") (pinfunction "-5V_B20") (pintype "power_in"))
    )
    (net (code "8") (name "/-12V") (class "Default")
      (node (ref "CONN1") (pin "B23") (pinfunction "-12V_B23") (pintype "power_in"))
    )
    (net (code "9") (name "/A0") (class "Default")
      (node (ref "CONN1") (pin "A9") (pinfunction "A0_A9") (pintype "bidirectional"))
      (node (ref "RN4") (pin "1") (pinfunction "1_1") (pintype "passive"))
    )
    (net (code "10") (name "/A1") (class "Default")
      (node (ref "CONN1") (pin "A10") (pinfunction "A1_A10") (pintype "bidirectional"))
      (node (ref "RN4") (pin "2") (pinfunction "1_2") (pintype "passive"))
    )
    (net (code "11") (name "/A2") (class "Default")
      (node (ref "CONN1") (pin "A11") (pinfunction "A2_A11") (pintype "bidirectional"))
      (node (ref "RN4") (pin "3") (pinfunction "1_3") (pintype "passive"))
    )
    (net (code "12") (name "/A3") (class "Default")
      (node (ref "CONN1") (pin "A12") (pinfunction "A3_A12") (pintype "bidirectional"))
      (node (ref "RN4") (pin "4") (pinfunction "1_4") (pintype "passive"))
    )
    (net (code "13") (name "/A4") (class "Default")
      (node (ref "CONN1") (pin "A24") (pinfunction "A4_A24") (pintype "bidirectional"))
      (node (ref "RN5") (pin "4") (pinfunction "1_4") (pintype "passive"))
    )
    (net (code "14") (name "/A5") (class "Default")
      (node (ref "CONN1") (pin "A23") (pinfunction "A5_A23") (pintype "bidirectional"))
      (node (ref "RN5") (pin "3") (pinfunction "1_3") (pintype "passive"))
    )
    (net (code "15") (name "/A6") (class "Default")
      (node (ref "CONN1") (pin "A22") (pinfunction "A6_A22") (pintype "bidirectional"))
      (node (ref "RN5") (pin "2") (pinfunction "1_2") (pintype "passive"))
    )
    (net (code "16") (name "/A7") (class "Default")
      (node (ref "CONN1") (pin "A21") (pinfunction "A7_A21") (pintype "bidirectional"))
      (node (ref "RN5") (pin "1") (pinfunction "1_1") (pintype "passive"))
    )
    (net (code "17") (name "/A8") (class "Default")
      (node (ref "CONN1") (pin "B26") (pinfunction "A8_B26") (pintype "bidirectional"))
      (node (ref "RN6") (pin "1") (pinfunction "1_1") (pintype "passive"))
    )
    (net (code "18") (name "/A9") (class "Default")
      (node (ref "CONN1") (pin "A27") (pinfunction "A9_A27") (pintype "bidirectional"))
      (node (ref "RN6") (pin "2") (pinfunction "1_2") (pintype "passive"))
    )
    (net (code "19") (name "/A10") (class "Default")
      (node (ref "CONN1") (pin "B27") (pinfunction "A10_B27") (pintype "bidirectional"))
      (node (ref "RN6") (pin "3") (pinfunction "1_3") (pintype "passive"))
    )
    (net (code "20") (name "/A11") (class "Default")
      (node (ref "CONN1") (pin "A28") (pinfunction "A11_A28") (pintype "bidirectional"))
      (node (ref "RN6") (pin "4") (pinfunction "1_4") (pintype "passive"))
    )
    (net (code "21") (name "/A12") (class "Default")
      (node (ref "CONN1") (pin "A2") (pinfunction "A12_A2") (pintype "bidirectional"))
      (node (ref "RN3") (pin "4") (pinfunction "1_4") (pintype "passive"))
    )
    (net (code "22") (name "/A13") (class "Default")
      (node (ref "CONN1") (pin "B2") (pinfunction "A13_B2") (pintype "bidirectional"))
      (node (ref "RN3") (pin "3") (pinfunction "1_3") (pintype "passive"))
    )
    (net (code "23") (name "/A14") (class "Default")
      (node (ref "CONN1") (pin "A1") (pinfunction "A14_A1") (pintype "bidirectional"))
      (node (ref "RN3") (pin "2") (pinfunction "1_2") (pintype "passive"))
    )
    (net (code "24") (name "/A15") (class "Default")
      (node (ref "CONN1") (pin "B1") (pinfunction "A15_B1") (pintype "bidirectional"))
      (node (ref "RN3") (pin "1") (pinfunction "1_1") (pintype "passive"))
    )
    (net (code "25") (name "/ASDO") (class "Default")
      (node (ref "IC2") (pin "8") (pinfunction "__IO_6/FLASH_NCS/NCSO_8") (pintype "bidirectional"))
      (node (ref "U2") (pin "5") (pinfunction "ASDI_5") (pintype "input"))
    )
    (net (code "26") (name "/A_BUS_OE") (class "Default")
      (node (ref "IC10") (pin "19") (pinfunction "G_19") (pintype "input"))
      (node (ref "IC11") (pin "19") (pinfunction "G_19") (pintype "input"))
      (node (ref "IC2") (pin "10") (pinfunction "__IO_7_10") (pintype "bidirectional"))
      (node (ref "R25") (pin "2") (pinfunction "2_2") (pintype "passive"))
    )
    (net (code "27") (name "/CK") (class "Default")
      (node (ref "CONN1") (pin "A8") (pinfunction "CK_A8") (pintype "bidirectional"))
      (node (ref "RN1") (pin "1") (pinfunction "1_1") (pintype "passive"))
    )
    (net (code "28") (name "/CONF_DONE") (class "Default")
      (node (ref "IC2") (pin "92") (pinfunction "__CONF_DONE_92") (pintype "bidirectional"))
      (node (ref "TP4") (pin "TP") (pinfunction "TP_TP") (pintype "input"))
    )
    (net (code "29") (name "/CTRL_OE") (class "Default")
      (node (ref "IC2") (pin "129") (pinfunction "__IO_74_129") (pintype "bidirectional"))
      (node (ref "IC3") (pin "19") (pinfunction "G_19") (pintype "input"))
      (node (ref "R26") (pin "2") (pinfunction "2_2") (pintype "passive"))
    )
    (net (code "30") (name "/D0") (class "Default")
      (node (ref "CONN1") (pin "B6") (pinfunction "D0_B6") (pintype "bidirectional"))
      (node (ref "RN7") (pin "2") (pinfunction "1_2") (pintype "passive"))
    )
    (net (code "31") (name "/D1") (class "Default")
      (node (ref "CONN1") (pin "B7") (pinfunction "D1_B7") (pintype "bidirectional"))
      (node (ref "RN7") (pin "3") (pinfunction "1_3") (pintype "passive"))
    )
    (net (code "32") (name "/D2") (class "Default")
      (node (ref "CONN1") (pin "B8") (pinfunction "D2_B8") (pintype "bidirectional"))
      (node (ref "RN7") (pin "4") (pinfunction "1_4") (pintype "passive"))
    )
    (net (code "33") (name "/D3") (class "Default")
      (node (ref "CONN1") (pin "B11") (pinfunction "D3_B11") (pintype "bidirectional"))
      (node (ref "RN8") (pin "3") (pinfunction "1_3") (pintype "passive"))
    )
    (net (code "34") (name "/D4") (class "Default")
      (node (ref "CONN1") (pin "B12") (pinfunction "D4_B12") (pintype "bidirectional"))
      (node (ref "RN8") (pin "4") (pinfunction "1_4") (pintype "passive"))
    )
    (net (code "35") (name "/D5") (class "Default")
      (node (ref "CONN1") (pin "B10") (pinfunction "D5_B10") (pintype "bidirectional"))
      (node (ref "RN8") (pin "2") (pinfunction "1_2") (pintype "passive"))
    )
    (net (code "36") (name "/D6") (class "Default")
      (node (ref "CONN1") (pin "B9") (pinfunction "D6_B9") (pintype "bidirectional"))
      (node (ref "RN8") (pin "1") (pinfunction "1_1") (pintype "passive"))
    )
    (net (code "37") (name "/D7") (class "Default")
      (node (ref "CONN1") (pin "B3") (pinfunction "D7_B3") (pintype "bidirectional"))
      (node (ref "RN7") (pin "1") (pinfunction "1_1") (pintype "passive"))
    )
    (net (code "38") (name "/DATA0") (class "Default")
      (node (ref "IC2") (pin "13") (pinfunction "__DATA0_13") (pintype "bidirectional"))
      (node (ref "U2") (pin "2") (pinfunction "DATA_2") (pintype "output"))
    )
    (net (code "39") (name "/DCLK") (class "Default")
      (node (ref "IC2") (pin "12") (pinfunction "__DCLK_12") (pintype "input"))
      (node (ref "U2") (pin "6") (pinfunction "DCLK_6") (pintype "input"))
    )
    (net (code "40") (name "/D_BUS_DIR") (class "Default")
      (node (ref "IC2") (pin "6") (pinfunction "__IO_4/DATA/ADSO_6") (pintype "bidirectional"))
      (node (ref "IC4") (pin "1") (pinfunction "DIR_1") (pintype "input"))
    )
    (net (code "41") (name "/D_BUS_OE") (class "Default")
      (node (ref "IC2") (pin "7") (pinfunction "__IO_5_7") (pintype "bidirectional"))
      (node (ref "IC4") (pin "19") (pinfunction "G_19") (pintype "input"))
      (node (ref "R24") (pin "2") (pinfunction "2_2") (pintype "passive"))
    )
    (net (code "42") (name "/ESP_EN") (class "Default")
      (node (ref "C1") (pin "2") (pinfunction "2_2") (pintype "passive"))
      (node (ref "R2") (pin "1") (pinfunction "1_1") (pintype "passive"))
      (node (ref "S1") (pin "B2") (pinfunction "2_B2") (pintype "passive"))
      (node (ref "U1") (pin "3") (pinfunction "EN_3") (pintype "bidirectional"))
    )
    (net (code "43") (name "/ESP_IO0") (class "Default")
      (node (ref "C2") (pin "2") (pinfunction "2_2") (pintype "passive"))
      (node (ref "R3") (pin "1") (pinfunction "1_1") (pintype "passive"))
      (node (ref "S2") (pin "B2") (pinfunction "2_B2") (pintype "passive"))
      (node (ref "U1") (pin "25") (pinfunction "IO0_25") (pintype "bidirectional"))
    )
    (net (code "44") (name "/ESP_IO14") (class "Default")
      (node (ref "IC2") (pin "142") (pinfunction "__IO_82_142") (pintype "bidirectional"))
      (node (ref "U1") (pin "13") (pinfunction "IO14_13") (pintype "bidirectional"))
    )
    (net (code "45") (name "/ESP_IO25") (class "Default")
      (node (ref "IC2") (pin "137") (pinfunction "__IO_79_137") (pintype "bidirectional"))
      (node (ref "U1") (pin "10") (pinfunction "IO25_10") (pintype "bidirectional"))
    )
    (net (code "46") (name "/ESP_IO26") (class "Default")
      (node (ref "IC2") (pin "138") (pinfunction "__IO_80_138") (pintype "bidirectional"))
      (node (ref "U1") (pin "11") (pinfunction "IO26_11") (pintype "bidirectional"))
    )
    (net (code "47") (name "/ESP_IO27") (class "Default")
      (node (ref "IC2") (pin "141") (pinfunction "__IO_81_141") (pintype "bidirectional"))
      (node (ref "U1") (pin "12") (pinfunction "IO27_12") (pintype "bidirectional"))
    )
    (net (code "48") (name "/ESP_MISO") (class "Default")
      (node (ref "IC2") (pin "2") (pinfunction "__IO_2_2") (pintype "bidirectional"))
      (node (ref "U1") (pin "31") (pinfunction "IO19_31") (pintype "bidirectional"))
    )
    (net (code "49") (name "/ESP_MOSI") (class "Default")
      (node (ref "IC2") (pin "144") (pinfunction "__IO_84_144") (pintype "bidirectional"))
      (node (ref "U1") (pin "37") (pinfunction "IO23_37") (pintype "bidirectional"))
    )
    (net (code "50") (name "/ESP_NCS0") (class "Default")
      (node (ref "IC2") (pin "3") (pinfunction "__IO_3_3") (pintype "bidirectional"))
      (node (ref "U1") (pin "29") (pinfunction "IO5_29") (pintype "bidirectional"))
    )
    (net (code "51") (name "/ESP_QDH") (class "Default")
      (node (ref "IC2") (pin "1") (pinfunction "__IO_1_1") (pintype "bidirectional"))
      (node (ref "U1") (pin "33") (pinfunction "IO21_33") (pintype "bidirectional"))
    )
    (net (code "52") (name "/ESP_QWP") (class "Default")
      (node (ref "IC2") (pin "143") (pinfunction "__IO_83_143") (pintype "bidirectional"))
      (node (ref "U1") (pin "36") (pinfunction "IO22_36") (pintype "bidirectional"))
    )
    (net (code "53") (name "/ESP_RX") (class "Default")
      (node (ref "IC7") (pin "6") (pinfunction "TX_6") (pintype "output"))
      (node (ref "U1") (pin "34") (pinfunction "RXD0_34") (pintype "bidirectional"))
    )
    (net (code "54") (name "/ESP_SCK") (class "Default")
      (node (ref "IC2") (pin "23") (pinfunction "__CLK1_23") (pintype "input"))
      (node (ref "U1") (pin "30") (pinfunction "IO18_30") (pintype "bidirectional"))
    )
    (net (code "55") (name "/ESP_TX") (class "Default")
      (node (ref "IC7") (pin "7") (pinfunction "RX_7") (pintype "input"))
      (node (ref "U1") (pin "35") (pinfunction "TXD0_35") (pintype "bidirectional"))
    )
    (net (code "56") (name "/FORCE_INT") (class "Default")
      (node (ref "IC2") (pin "53") (pinfunction "__IO_26_53") (pintype "bidirectional"))
      (node (ref "Q2") (pin "1") (pinfunction "G_1") (pintype "passive"))
    )
    (net (code "57") (name "/FORCE_RESET") (class "Default")
      (node (ref "IC2") (pin "67") (pinfunction "__IO_35_67") (pintype "bidirectional"))
      (node (ref "Q1") (pin "1") (pinfunction "G_1") (pintype "passive"))
    )
    (net (code "58") (name "/FORCE_ROMCS") (class "Default")
      (node (ref "IC2") (pin "132") (pinfunction "__IO_75_132") (pintype "bidirectional"))
      (node (ref "Q3") (pin "1") (pinfunction "G_1") (pintype "passive"))
    )
    (net (code "59") (name "/FR1") (class "Default")
      (node (ref "Q3") (pin "3") (pinfunction "D_3") (pintype "passive"))
      (node (ref "Q4") (pin "1") (pinfunction "G_1") (pintype "passive"))
      (node (ref "R5") (pin "2") (pinfunction "2_2") (pintype "passive"))
    )
    (net (code "60") (name "/INT") (class "Default")
      (node (ref "CONN1") (pin "B13") (pinfunction "INT_B13") (pintype "bidirectional"))
      (node (ref "Q2") (pin "3") (pinfunction "D_3") (pintype "passive"))
      (node (ref "RN1") (pin "2") (pinfunction "1_2") (pintype "passive"))
    )
    (net (code "61") (name "/IORQ") (class "Default")
      (node (ref "CONN1") (pin "B17") (pinfunction "IORQ_B17") (pintype "bidirectional"))
      (node (ref "RN1") (pin "4") (pinfunction "1_4") (pintype "passive"))
    )
    (net (code "62") (name "/LED1") (class "Default")
      (node (ref "R21") (pin "2") (pinfunction "2_2") (pintype "passive"))
      (node (ref "U1") (pin "8") (pinfunction "IO32_8") (pintype "bidirectional"))
    )
    (net (code "63") (name "/LED2") (class "Default")
      (node (ref "R22") (pin "2") (pinfunction "2_2") (pintype "passive"))
      (node (ref "U1") (pin "9") (pinfunction "IO33_9") (pintype "bidirectional"))
    )
    (net (code "64") (name "/M1") (class "Default")
      (node (ref "CONN1") (pin "B24") (pinfunction "M1_B24") (pintype "bidirectional"))
      (node (ref "RN2") (pin "3") (pinfunction "1_3") (pintype "passive"))
    )
    (net (code "65") (name "/MREQ") (class "Default")
      (node (ref "CONN1") (pin "B16") (pinfunction "MREQ_B16") (pintype "bidirectional"))
      (node (ref "RN1") (pin "3") (pinfunction "1_3") (pintype "passive"))
    )
    (net (code "66") (name "/NCONFIG") (class "Default")
      (node (ref "IC2") (pin "14") (pinfunction "__NCONFIG_14") (pintype "bidirectional"))
      (node (ref "R7") (pin "1") (pinfunction "1_1") (pintype "passive"))
    )
    (net (code "67") (name "/NCSO") (class "Default")
      (node (ref "IC2") (pin "11") (pinfunction "__IO_8_11") (pintype "bidirectional"))
      (node (ref "U2") (pin "1") (pinfunction "NCS_1") (pintype "input"))
    )
    (net (code "68") (name "/RD") (class "Default")
      (node (ref "CONN1") (pin "B18") (pinfunction "RD_B18") (pintype "bidirectional"))
      (node (ref "RN2") (pin "1") (pinfunction "1_1") (pintype "passive"))
    )
    (net (code "69") (name "/RESET") (class "Default")
      (node (ref "CONN1") (pin "A20") (pinfunction "RESET_A20") (pintype "bidirectional"))
      (node (ref "Q1") (pin "3") (pinfunction "D_3") (pintype "passive"))
    )
    (net (code "70") (name "/RFSH") (class "Default")
      (node (ref "CONN1") (pin "B25") (pinfunction "RFSH_B25") (pintype "bidirectional"))
      (node (ref "RN2") (pin "4") (pinfunction "1_4") (pintype "passive"))
    )
    (net (code "71") (name "/ROMCS") (class "Default")
      (node (ref "CONN1") (pin "A25") (pinfunction "ROMCS_A25") (pintype "bidirectional"))
      (node (ref "Q4") (pin "3") (pinfunction "D_3") (pintype "passive"))
    )
    (net (code "72") (name "/SDMMC_CK") (class "Default")
      (node (ref "SD1") (pin "5") (pinfunction "CLK(SCLK)_5") (pintype "input"))
      (node (ref "U1") (pin "20") (pinfunction "CLK_20") (pintype "bidirectional"))
    )
    (net (code "73") (name "/SDMMC_CMD") (class "Default")
      (node (ref "SD1") (pin "3") (pinfunction "CMD(DI)_3") (pintype "bidirectional"))
      (node (ref "U1") (pin "19") (pinfunction "CMD_19") (pintype "bidirectional"))
    )
    (net (code "74") (name "/SDMMC_D0") (class "Default")
      (node (ref "SD1") (pin "7") (pinfunction "DAT0(DO)_7") (pintype "bidirectional"))
      (node (ref "U1") (pin "21") (pinfunction "SDO_21") (pintype "bidirectional"))
    )
    (net (code "75") (name "/SDMMC_D1") (class "Default")
      (node (ref "SD1") (pin "8") (pinfunction "DAT1_8") (pintype "bidirectional"))
      (node (ref "U1") (pin "22") (pinfunction "SD1_22") (pintype "bidirectional"))
    )
    (net (code "76") (name "/SDMMC_D2") (class "Default")
      (node (ref "SD1") (pin "1") (pinfunction "DAT2_1") (pintype "bidirectional"))
      (node (ref "U1") (pin "17") (pinfunction "SD2_17") (pintype "bidirectional"))
    )
    (net (code "77") (name "/SDMMC_D3") (class "Default")
      (node (ref "SD1") (pin "2") (pinfunction "CD/DAT3(~{CS})_2") (pintype "bidirectional"))
      (node (ref "U1") (pin "18") (pinfunction "SD3_18") (pintype "bidirectional"))
    )
    (net (code "78") (name "/SDMMC_DET") (class "Default")
      (node (ref "R1") (pin "2") (pinfunction "2_2") (pintype "passive"))
      (node (ref "SD1") (pin "A") (pinfunction "A_A") (pintype "passive"))
      (node (ref "U1") (pin "23") (pinfunction "IO15_23") (pintype "bidirectional"))
    )
    (net (code "79") (name "/SD_A0") (class "Default")
      (node (ref "IC2") (pin "87") (pinfunction "__IO_51_87") (pintype "bidirectional"))
      (node (ref "IC9") (pin "23") (pinfunction "A0_23") (pintype "input"))
    )
    (net (code "80") (name "/SD_A1") (class "Default")
      (node (ref "IC2") (pin "86") (pinfunction "__IO_50_86") (pintype "bidirectional"))
      (node (ref "IC9") (pin "24") (pinfunction "A1_24") (pintype "input"))
    )
    (net (code "81") (name "/SD_A2") (class "Default")
      (node (ref "IC2") (pin "85") (pinfunction "__IO_49_85") (pintype "bidirectional"))
      (node (ref "IC9") (pin "25") (pinfunction "A2_25") (pintype "input"))
    )
    (net (code "82") (name "/SD_A3") (class "Default")
      (node (ref "IC2") (pin "84") (pinfunction "__IO_48_84") (pintype "bidirectional"))
      (node (ref "IC9") (pin "26") (pinfunction "A3_26") (pintype "input"))
    )
    (net (code "83") (name "/SD_A4") (class "Default")
      (node (ref "IC2") (pin "76") (pinfunction "__IO_44_76") (pintype "bidirectional"))
      (node (ref "IC9") (pin "29") (pinfunction "A4_29") (pintype "input"))
    )
    (net (code "84") (name "/SD_A5") (class "Default")
      (node (ref "IC2") (pin "77") (pinfunction "__IO_45_77") (pintype "bidirectional"))
      (node (ref "IC9") (pin "30") (pinfunction "A5_30") (pintype "input"))
    )
    (net (code "85") (name "/SD_A6") (class "Default")
      (node (ref "IC2") (pin "80") (pinfunction "__IO_46_80") (pintype "bidirectional"))
      (node (ref "IC9") (pin "31") (pinfunction "A6_31") (pintype "input"))
    )
    (net (code "86") (name "/SD_A7") (class "Default")
      (node (ref "IC2") (pin "83") (pinfunction "__IO_47_83") (pintype "bidirectional"))
      (node (ref "IC9") (pin "32") (pinfunction "A7_32") (pintype "input"))
    )
    (net (code "87") (name "/SD_A8") (class "Default")
      (node (ref "IC2") (pin "120") (pinfunction "__IO_67_120") (pintype "bidirectional"))
      (node (ref "IC9") (pin "33") (pinfunction "A8_33") (pintype "input"))
    )
    (net (code "88") (name "/SD_A9") (class "Default")
      (node (ref "IC2") (pin "121") (pinfunction "__IO_68_121") (pintype "bidirectional"))
      (node (ref "IC9") (pin "34") (pinfunction "A9_34") (pintype "input"))
    )
    (net (code "89") (name "/SD_A10") (class "Default")
      (node (ref "IC2") (pin "98") (pinfunction "__IO_52_98") (pintype "bidirectional"))
      (node (ref "IC9") (pin "22") (pinfunction "A10_22") (pintype "input"))
    )
    (net (code "90") (name "/SD_A11") (class "Default")
      (node (ref "IC2") (pin "124") (pinfunction "__IO_69_124") (pintype "bidirectional"))
      (node (ref "IC9") (pin "35") (pinfunction "A11_35") (pintype "input"))
    )
    (net (code "91") (name "/SD_A12") (class "Default")
      (node (ref "IC2") (pin "125") (pinfunction "__IO_70_125") (pintype "bidirectional"))
      (node (ref "IC9") (pin "36") (pinfunction "A12_36") (pintype "input"))
    )
    (net (code "92") (name "/SD_BA0") (class "Default")
      (node (ref "IC2") (pin "100") (pinfunction "__IO_54_100") (pintype "bidirectional"))
      (node (ref "IC9") (pin "20") (pinfunction "BA0_20") (pintype "input"))
    )
    (net (code "93") (name "/SD_BA1") (class "Default")
      (node (ref "IC2") (pin "99") (pinfunction "__IO_53_99") (pintype "bidirectional"))
      (node (ref "IC9") (pin "21") (pinfunction "BA1_21") (pintype "input"))
    )
    (net (code "94") (name "/SD_CK") (class "Default")
      (node (ref "IC2") (pin "127") (pinfunction "__IO_72_127") (pintype "bidirectional"))
      (node (ref "IC9") (pin "38") (pinfunction "CLK_38") (pintype "input"))
    )
    (net (code "95") (name "/SD_CKE") (class "Default")
      (node (ref "IC2") (pin "126") (pinfunction "__IO_71_126") (pintype "bidirectional"))
      (node (ref "IC9") (pin "37") (pinfunction "CKE_37") (pintype "input"))
    )
    (net (code "96") (name "/SD_CS") (class "Default")
      (node (ref "IC2") (pin "101") (pinfunction "__IO_55_101") (pintype "bidirectional"))
      (node (ref "IC9") (pin "19") (pinfunction "\\CS_19") (pintype "input"))
    )
    (net (code "97") (name "/SD_DQ0") (class "Default")
      (node (ref "IC2") (pin "119") (pinfunction "__IO_66_119") (pintype "bidirectional"))
      (node (ref "IC9") (pin "2") (pinfunction "DQ0_2") (pintype "tri_state"))
    )
    (net (code "98") (name "/SD_DQ1") (class "Default")
      (node (ref "IC2") (pin "115") (pinfunction "__IO_65_115") (pintype "bidirectional"))
      (node (ref "IC9") (pin "4") (pinfunction "DQ1_4") (pintype "tri_state"))
    )
    (net (code "99") (name "/SD_DQ2") (class "Default")
      (node (ref "IC2") (pin "114") (pinfunction "__IO_64_114") (pintype "bidirectional"))
      (node (ref "IC9") (pin "5") (pinfunction "DQ2_5") (pintype "tri_state"))
    )
    (net (code "100") (name "/SD_DQ3") (class "Default")
      (node (ref "IC2") (pin "113") (pinfunction "__IO_63_113") (pintype "bidirectional"))
      (node (ref "IC9") (pin "7") (pinfunction "DQ3_7") (pintype "tri_state"))
    )
    (net (code "101") (name "/SD_DQ4") (class "Default")
      (node (ref "IC2") (pin "112") (pinfunction "__IO_62_112") (pintype "bidirectional"))
      (node (ref "IC9") (pin "8") (pinfunction "DQ4_8") (pintype "tri_state"))
    )
    (net (code "102") (name "/SD_DQ5") (class "Default")
      (node (ref "IC2") (pin "111") (pinfunction "__IO_61_111") (pintype "bidirectional"))
      (node (ref "IC9") (pin "10") (pinfunction "DQ5_10") (pintype "tri_state"))
    )
    (net (code "103") (name "/SD_DQ6") (class "Default")
      (node (ref "IC2") (pin "110") (pinfunction "__IO_60_110") (pintype "bidirectional"))
      (node (ref "IC9") (pin "11") (pinfunction "DQ6_11") (pintype "tri_state"))
    )
    (net (code "104") (name "/SD_DQ7") (class "Default")
      (node (ref "IC2") (pin "106") (pinfunction "__IO_59_106") (pintype "bidirectional"))
      (node (ref "IC9") (pin "13") (pinfunction "DQ7_13") (pintype "tri_state"))
    )
    (net (code "105") (name "/SD_DQMH") (class "Default")
      (node (ref "IC2") (pin "128") (pinfunction "__IO_73_128") (pintype "bidirectional"))
      (node (ref "IC9") (pin "39") (pinfunction "DQMH_39") (pintype "input"))
    )
    (net (code "106") (name "/SD_NCAS") (class "Default")
      (node (ref "IC2") (pin "104") (pinfunction "__IO_57_104") (pintype "bidirectional"))
      (node (ref "IC9") (pin "17") (pinfunction "~{CAS}_17") (pintype "input"))
    )
    (net (code "107") (name "/SD_NRAS") (class "Default")
      (node (ref "IC2") (pin "103") (pinfunction "__IO_56_103") (pintype "bidirectional"))
      (node (ref "IC9") (pin "18") (pinfunction "~{RAS}_18") (pintype "input"))
    )
    (net (code "108") (name "/SD_NWE") (class "Default")
      (node (ref "IC2") (pin "105") (pinfunction "__IO_58_105") (pintype "bidirectional"))
      (node (ref "IC9") (pin "16") (pinfunction "~{WE}_16") (pintype "input"))
    )
    (net (code "109") (name "/SW1") (class "Default")
      (node (ref "C42") (pin "1") (pinfunction "1_1") (pintype "passive"))
      (node (ref "IC5") (pin "3") (pinfunction "SW_3") (pintype "passive"))
      (node (ref "L1") (pin "P$1") (pinfunction "1_P$1") (pintype "passive"))
    )
    (net (code "110") (name "/SW2") (class "Default")
      (node (ref "C43") (pin "1") (pinfunction "1_1") (pintype "passive"))
      (node (ref "IC6") (pin "3") (pinfunction "SW_3") (pintype "passive"))
      (node (ref "L2") (pin "P$1") (pinfunction "1_P$1") (pintype "passive"))
    )
    (net (code "111") (name "/SWITCH") (class "Default")
      (node (ref "R4") (pin "1") (pinfunction "1_1") (pintype "passive"))
      (node (ref "S3") (pin "B2") (pinfunction "2_B2") (pintype "passive"))
      (node (ref "U1") (pin "6") (pinfunction "IO34_6") (pintype "input"))
    )
    (net (code "112") (name "/TCK") (class "Default")
      (node (ref "CONN2") (pin "1") (pinfunction "1_1") (pintype "passive"))
      (node (ref "IC2") (pin "16") (pinfunction "__TCK_16") (pintype "bidirectional"))
      (node (ref "R10") (pin "1") (pinfunction "1_1") (pintype "passive"))
    )
    (net (code "113") (name "/TDI") (class "Default")
      (node (ref "CONN2") (pin "9") (pinfunction "9_9") (pintype "passive"))
      (node (ref "IC2") (pin "15") (pinfunction "__TDI_15") (pintype "bidirectional"))
    )
    (net (code "114") (name "/TDO") (class "Default")
      (node (ref "CONN2") (pin "3") (pinfunction "3_3") (pintype "passive"))
      (node (ref "IC2") (pin "20") (pinfunction "__TDO_20") (pintype "bidirectional"))
      (node (ref "R8") (pin "1") (pinfunction "1_1") (pintype "passive"))
    )
    (net (code "115") (name "/TMS") (class "Default")
      (node (ref "CONN2") (pin "5") (pinfunction "5_5") (pintype "passive"))
      (node (ref "IC2") (pin "18") (pinfunction "__TMS_18") (pintype "bidirectional"))
      (node (ref "R9") (pin "1") (pinfunction "1_1") (pintype "passive"))
    )
    (net (code "116") (name "/VREG") (class "Default")
      (node (ref "C31") (pin "2") (pinfunction "2_2") (pintype "passive"))
      (node (ref "C32") (pin "2") (pinfunction "2_2") (pintype "passive"))
      (node (ref "C33") (pin "2") (pinfunction "2_2") (pintype "passive"))
      (node (ref "C34") (pin "2") (pinfunction "2_2") (pintype "passive"))
      (node (ref "IC5") (pin "2") (pinfunction "IN_2") (pintype "power_in"))
      (node (ref "IC6") (pin "2") (pinfunction "IN_2") (pintype "power_in"))
      (node (ref "SJ1") (pin "2") (pinfunction "2_2") (pintype "passive"))
    )
    (net (code "117") (name "/WR") (class "Default")
      (node (ref "CONN1") (pin "B19") (pinfunction "WR_B19") (pintype "bidirectional"))
      (node (ref "RN2") (pin "2") (pinfunction "1_2") (pintype "passive"))
    )
    (net (code "118") (name "/XCK") (class "Default")
      (node (ref "IC2") (pin "54") (pinfunction "__IO_27_54") (pintype "bidirectional"))
      (node (ref "IC3") (pin "18") (pinfunction "B1_18") (pintype "bidirectional"))
    )
    (net (code "119") (name "/XD0") (class "Default")
      (node (ref "IC2") (pin "43") (pinfunction "__IO_19_43") (pintype "bidirectional"))
      (node (ref "IC4") (pin "17") (pinfunction "B2_17") (pintype "bidirectional"))
    )
    (net (code "120") (name "/XD1") (class "Default")
      (node (ref "IC2") (pin "44") (pinfunction "__IO_20_44") (pintype "bidirectional"))
      (node (ref "IC4") (pin "16") (pinfunction "B3_16") (pintype "bidirectional"))
    )
    (net (code "121") (name "/XD2") (class "Default")
      (node (ref "IC2") (pin "46") (pinfunction "__IO_21_46") (pintype "bidirectional"))
      (node (ref "IC4") (pin "15") (pinfunction "B4_15") (pintype "bidirectional"))
    )
    (net (code "122") (name "/XD3") (class "Default")
      (node (ref "IC2") (pin "51") (pinfunction "__IO_24_51") (pintype "bidirectional"))
      (node (ref "IC4") (pin "12") (pinfunction "B7_12") (pintype "bidirectional"))
    )
    (net (code "123") (name "/XD4") (class "Default")
      (node (ref "IC2") (pin "52") (pinfunction "__IO_25_52") (pintype "bidirectional"))
      (node (ref "IC4") (pin "11") (pinfunction "B8_11") (pintype "bidirectional"))
    )
    (net (code "124") (name "/XD5") (class "Default")
      (node (ref "IC2") (pin "50") (pinfunction "__IO_23_50") (pintype "bidirectional"))
      (node (ref "IC4") (pin "13") (pinfunction "B6_13") (pintype "bidirectional"))
    )
    (net (code "125") (name "/XD6") (class "Default")
      (node (ref "IC2") (pin "49") (pinfunction "__IO_22_49") (pintype "bidirectional"))
      (node (ref "IC4") (pin "14") (pinfunction "B5_14") (pintype "bidirectional"))
    )
    (net (code "126") (name "/XD7") (class "Default")
      (node (ref "IC2") (pin "42") (pinfunction "__IO_18_42") (pintype "bidirectional"))
      (node (ref "IC4") (pin "18") (pinfunction "B1_18") (pintype "bidirectional"))
    )
    (net (code "127") (name "/XINT") (class "Default")
      (node (ref "IC2") (pin "55") (pinfunction "__IO_28_55") (pintype "bidirectional"))
      (node (ref "IC3") (pin "17") (pinfunction "B2_17") (pintype "bidirectional"))
    )
    (net (code "128") (name "/XIORQ") (class "Default")
      (node (ref "IC2") (pin "59") (pinfunction "__IO_30_59") (pintype "bidirectional"))
      (node (ref "IC3") (pin "15") (pinfunction "B4_15") (pintype "bidirectional"))
    )
    (net (code "129") (name "/XM1") (class "Default")
      (node (ref "IC2") (pin "65") (pinfunction "__IO_33_65") (pintype "bidirectional"))
      (node (ref "IC3") (pin "12") (pinfunction "B7_12") (pintype "bidirectional"))
    )
    (net (code "130") (name "/XMREQ") (class "Default")
      (node (ref "IC2") (pin "58") (pinfunction "__IO_29_58") (pintype "bidirectional"))
      (node (ref "IC3") (pin "16") (pinfunction "B3_16") (pintype "bidirectional"))
    )
    (net (code "131") (name "/XRD") (class "Default")
      (node (ref "IC2") (pin "60") (pinfunction "__IO_31_60") (pintype "bidirectional"))
      (node (ref "IC3") (pin "14") (pinfunction "B5_14") (pintype "bidirectional"))
    )
    (net (code "132") (name "/XRFSH") (class "Default")
      (node (ref "IC2") (pin "66") (pinfunction "__IO_34_66") (pintype "bidirectional"))
      (node (ref "IC3") (pin "11") (pinfunction "B8_11") (pintype "bidirectional"))
    )
    (net (code "133") (name "/XWR") (class "Default")
      (node (ref "IC2") (pin "64") (pinfunction "__IO_32_64") (pintype "bidirectional"))
      (node (ref "IC3") (pin "13") (pinfunction "B6_13") (pintype "bidirectional"))
    )
    (net (code "134") (name "/ZX_A0") (class "Default")
      (node (ref "IC10") (pin "14") (pinfunction "B5_14") (pintype "bidirectional"))
      (node (ref "IC2") (pin "33") (pinfunction "__IO_14_33") (pintype "bidirectional"))
    )
    (net (code "135") (name "/ZX_A1") (class "Default")
      (node (ref "IC10") (pin "13") (pinfunction "B6_13") (pintype "bidirectional"))
      (node (ref "IC2") (pin "34") (pinfunction "__IO_15_34") (pintype "bidirectional"))
    )
    (net (code "136") (name "/ZX_A2") (class "Default")
      (node (ref "IC10") (pin "12") (pinfunction "B7_12") (pintype "bidirectional"))
      (node (ref "IC2") (pin "38") (pinfunction "__IO_16_38") (pintype "bidirectional"))
    )
    (net (code "137") (name "/ZX_A3") (class "Default")
      (node (ref "IC10") (pin "11") (pinfunction "B8_11") (pintype "bidirectional"))
      (node (ref "IC2") (pin "39") (pinfunction "__IO_17_39") (pintype "bidirectional"))
    )
    (net (code "138") (name "/ZX_A4") (class "Default")
      (node (ref "IC11") (pin "15") (pinfunction "B4_15") (pintype "bidirectional"))
      (node (ref "IC2") (pin "71") (pinfunction "__IO_39_71") (pintype "bidirectional"))
    )
    (net (code "139") (name "/ZX_A5") (class "Default")
      (node (ref "IC11") (pin "16") (pinfunction "B3_16") (pintype "bidirectional"))
      (node (ref "IC2") (pin "70") (pinfunction "__IO_38_70") (pintype "bidirectional"))
    )
    (net (code "140") (name "/ZX_A6") (class "Default")
      (node (ref "IC11") (pin "17") (pinfunction "B2_17") (pintype "bidirectional"))
      (node (ref "IC2") (pin "69") (pinfunction "__IO_37_69") (pintype "bidirectional"))
    )
    (net (code "141") (name "/ZX_A7") (class "Default")
      (node (ref "IC11") (pin "18") (pinfunction "B1_18") (pintype "bidirectional"))
      (node (ref "IC2") (pin "68") (pinfunction "__IO_36_68") (pintype "bidirectional"))
    )
    (net (code "142") (name "/ZX_A8") (class "Default")
      (node (ref "IC11") (pin "14") (pinfunction "B5_14") (pintype "bidirectional"))
      (node (ref "IC2") (pin "72") (pinfunction "__IO_40_72") (pintype "bidirectional"))
    )
    (net (code "143") (name "/ZX_A9") (class "Default")
      (node (ref "IC11") (pin "13") (pinfunction "B6_13") (pintype "bidirectional"))
      (node (ref "IC2") (pin "73") (pinfunction "__IO_41_73") (pintype "bidirectional"))
    )
    (net (code "144") (name "/ZX_A10") (class "Default")
      (node (ref "IC11") (pin "12") (pinfunction "B7_12") (pintype "bidirectional"))
      (node (ref "IC2") (pin "74") (pinfunction "__IO_42_74") (pintype "bidirectional"))
    )
    (net (code "145") (name "/ZX_A11") (class "Default")
      (node (ref "IC11") (pin "11") (pinfunction "B8_11") (pintype "bidirectional"))
      (node (ref "IC2") (pin "75") (pinfunction "__IO_43_75") (pintype "bidirectional"))
    )
    (net (code "146") (name "/ZX_A12") (class "Default")
      (node (ref "IC10") (pin "15") (pinfunction "B4_15") (pintype "bidirectional"))
      (node (ref "IC2") (pin "32") (pinfunction "__IO_13_32") (pintype "bidirectional"))
    )
    (net (code "147") (name "/ZX_A13") (class "Default")
      (node (ref "IC10") (pin "16") (pinfunction "B3_16") (pintype "bidirectional"))
      (node (ref "IC2") (pin "31") (pinfunction "__IO_12_31") (pintype "bidirectional"))
    )
    (net (code "148") (name "/ZX_A14") (class "Default")
      (node (ref "IC10") (pin "17") (pinfunction "B2_17") (pintype "bidirectional"))
      (node (ref "IC2") (pin "30") (pinfunction "__IO_11_30") (pintype "bidirectional"))
    )
    (net (code "149") (name "/ZX_A15") (class "Default")
      (node (ref "IC10") (pin "18") (pinfunction "B1_18") (pintype "bidirectional"))
      (node (ref "IC2") (pin "28") (pinfunction "__IO_10_28") (pintype "bidirectional"))
    )
    (net (code "150") (name "GND") (class "Default")
      (node (ref "C1") (pin "1") (pinfunction "1_1") (pintype "passive"))
      (node (ref "C10") (pin "2") (pinfunction "2_2") (pintype "passive"))
      (node (ref "C11") (pin "2") (pinfunction "2_2") (pintype "passive"))
      (node (ref "C12") (pin "2") (pinfunction "2_2") (pintype "passive"))
      (node (ref "C13") (pin "2") (pinfunction "2_2") (pintype "passive"))
      (node (ref "C14") (pin "2") (pinfunction "2_2") (pintype "passive"))
      (node (ref "C15") (pin "2") (pinfunction "2_2") (pintype "passive"))
      (node (ref "C16") (pin "2") (pinfunction "2_2") (pintype "passive"))
      (node (ref "C17") (pin "2") (pinfunction "2_2") (pintype "passive"))
      (node (ref "C18") (pin "2") (pinfunction "2_2") (pintype "passive"))
      (node (ref "C19") (pin "2") (pinfunction "2_2") (pintype "passive"))
      (node (ref "C2") (pin "1") (pinfunction "1_1") (pintype "passive"))
      (node (ref "C20") (pin "2") (pinfunction "2_2") (pintype "passive"))
      (node (ref "C21") (pin "2") (pinfunction "2_2") (pintype "passive"))
      (node (ref "C22") (pin "2") (pinfunction "2_2") (pintype "passive"))
      (node (ref "C23") (pin "2") (pinfunction "2_2") (pintype "passive"))
      (node (ref "C24") (pin "2") (pinfunction "2_2") (pintype "passive"))
      (node (ref "C25") (pin "2") (pinfunction "2_2") (pintype "passive"))
      (node (ref "C26") (pin "2") (pinfunction "2_2") (pintype "passive"))
      (node (ref "C27") (pin "2") (pinfunction "2_2") (pintype "passive"))
      (node (ref "C28") (pin "2") (pinfunction "2_2") (pintype "passive"))
      (node (ref "C29") (pin "2") (pinfunction "2_2") (pintype "passive"))
      (node (ref "C3") (pin "2") (pinfunction "2_2") (pintype "passive"))
      (node (ref "C30") (pin "2") (pinfunction "2_2") (pintype "passive"))
      (node (ref "C31") (pin "1") (pinfunction "1_1") (pintype "passive"))
      (node (ref "C32") (pin "1") (pinfunction "1_1") (pintype "passive"))
      (node (ref "C33") (pin "1") (pinfunction "1_1") (pintype "passive"))
      (node (ref "C34") (pin "1") (pinfunction "1_1") (pintype "passive"))
      (node (ref "C35") (pin "1") (pinfunction "1_1") (pintype "passive"))
      (node (ref "C36") (pin "1") (pinfunction "1_1") (pintype "passive"))
      (node (ref "C37") (pin "2") (pinfunction "2_2") (pintype "passive"))
      (node (ref "C38") (pin "1") (pinfunction "1_1") (pintype "passive"))
      (node (ref "C39") (pin "1") (pinfunction "1_1") (pintype "passive"))
      (node (ref "C4") (pin "2") (pinfunction "2_2") (pintype "passive"))
      (node (ref "C40") (pin "2") (pinfunction "2_2") (pintype "passive"))
      (node (ref "C41") (pin "2") (pinfunction "2_2") (pintype "passive"))
      (node (ref "C45") (pin "1") (pinfunction "1_1") (pintype "passive"))
      (node (ref "C46") (pin "1") (pinfunction "1_1") (pintype "passive"))
      (node (ref "C47") (pin "1") (pinfunction "1_1") (pintype "passive"))
      (node (ref "C48") (pin "2") (pinfunction "2_2") (pintype "passive"))
      (node (ref "C49") (pin "2") (pinfunction "2_2") (pintype "passive"))
      (node (ref "C5") (pin "2") (pinfunction "2_2") (pintype "passive"))
      (node (ref "C50") (pin "2") (pinfunction "2_2") (pintype "passive"))
      (node (ref "C51") (pin "2") (pinfunction "2_2") (pintype "passive"))
      (node (ref "C52") (pin "2") (pinfunction "2_2") (pintype "passive"))
      (node (ref "C53") (pin "2") (pinfunction "2_2") (pintype "passive"))
      (node (ref "C54") (pin "2") (pinfunction "2_2") (pintype "passive"))
      (node (ref "C55") (pin "2") (pinfunction "2_2") (pintype "passive"))
      (node (ref "C56") (pin "2") (pinfunction "2_2") (pintype "passive"))
      (node (ref "C57") (pin "MINUS") (pinfunction "-_MINUS") (pintype "passive"))
      (node (ref "C6") (pin "2") (pinfunction "2_2") (pintype "passive"))
      (node (ref "C60") (pin "MINUS") (pinfunction "-_MINUS") (pintype "passive"))
      (node (ref "C7") (pin "2") (pinfunction "2_2") (pintype "passive"))
      (node (ref "C8") (pin "2") (pinfunction "2_2") (pintype "passive"))
      (node (ref "C9") (pin "2") (pinfunction "2_2") (pintype "passive"))
      (node (ref "CONN1") (pin "A14") (pinfunction "GND_A14") (pintype "power_in"))
      (node (ref "CONN1") (pin "A6") (pinfunction "GND_A6") (pintype "power_in"))
      (node (ref "CONN1") (pin "A7") (pinfunction "GND_A7") (pintype "power_in"))
      (node (ref "CONN2") (pin "10") (pinfunction "10_10") (pintype "passive"))
      (node (ref "CONN2") (pin "2") (pinfunction "2_2") (pintype "passive"))
      (node (ref "IC10") (pin "10") (pinfunction "GND_10") (pintype "power_in"))
      (node (ref "IC11") (pin "10") (pinfunction "GND_10") (pintype "power_in"))
      (node (ref "IC2") (pin "108") (pinfunction "__GNDA2_108") (pintype "power_in"))
      (node (ref "IC2") (pin "118") (pinfunction "__GND_12_118") (pintype "power_in"))
      (node (ref "IC2") (pin "123") (pinfunction "__GND_13_123") (pintype "power_in"))
      (node (ref "IC2") (pin "131") (pinfunction "__GND_14_131") (pintype "power_in"))
      (node (ref "IC2") (pin "140") (pinfunction "__GND_15_140") (pintype "power_in"))
      (node (ref "IC2") (pin "145") (pinfunction "TP_145") (pintype "bidirectional"))
      (node (ref "IC2") (pin "19") (pinfunction "__GND_2_19") (pintype "power_in"))
      (node (ref "IC2") (pin "21") (pinfunction "__NCE_21") (pintype "bidirectional"))
      (node (ref "IC2") (pin "22") (pinfunction "__GND_3_22") (pintype "power_in"))
      (node (ref "IC2") (pin "27") (pinfunction "__GND_4_27") (pintype "power_in"))
      (node (ref "IC2") (pin "36") (pinfunction "__GNDA1_36") (pintype "power_in"))
      (node (ref "IC2") (pin "4") (pinfunction "__GND_1_4") (pintype "power_in"))
      (node (ref "IC2") (pin "41") (pinfunction "__GND_5_41") (pintype "power_in"))
      (node (ref "IC2") (pin "48") (pinfunction "__GND_6_48") (pintype "power_in"))
      (node (ref "IC2") (pin "57") (pinfunction "__GND_7_57") (pintype "power_in"))
      (node (ref "IC2") (pin "63") (pinfunction "__GND_8_63") (pintype "power_in"))
      (node (ref "IC2") (pin "79") (pinfunction "__GND_9_79") (pintype "power_in"))
      (node (ref "IC2") (pin "82") (pinfunction "__GND_10_82") (pintype "power_in"))
      (node (ref "IC2") (pin "95") (pinfunction "__GND_11_95") (pintype "power_in"))
      (node (ref "IC2") (pin "96") (pinfunction "__MSEL1_96") (pintype "bidirectional"))
      (node (ref "IC3") (pin "10") (pinfunction "GND_10") (pintype "power_in"))
      (node (ref "IC4") (pin "10") (pinfunction "GND_10") (pintype "power_in"))
      (node (ref "IC5") (pin "4") (pinfunction "GND_4") (pintype "power_in"))
      (node (ref "IC6") (pin "4") (pinfunction "GND_4") (pintype "power_in"))
      (node (ref "IC7") (pin "3") (pinfunction "GND_3") (pintype "power_in"))
      (node (ref "IC8") (pin "2") (pinfunction "GND_2") (pintype "power_in"))
      (node (ref "IC9") (pin "12") (pinfunction "VSSQ_12") (pintype "power_in"))
      (node (ref "IC9") (pin "28") (pinfunction "VSS_28") (pintype "power_in"))
      (node (ref "IC9") (pin "41") (pinfunction "VSS_41") (pintype "power_in"))
      (node (ref "IC9") (pin "46") (pinfunction "VSSQ_46") (pintype "power_in"))
      (node (ref "IC9") (pin "52") (pinfunction "VSSQ_52") (pintype "power_in"))
      (node (ref "IC9") (pin "54") (pinfunction "VSS_54") (pintype "power_in"))
      (node (ref "IC9") (pin "6") (pinfunction "VSSQ_6") (pintype "power_in"))
      (node (ref "Q1") (pin "2") (pinfunction "S_2") (pintype "passive"))
      (node (ref "Q2") (pin "2") (pinfunction "S_2") (pintype "passive"))
      (node (ref "Q3") (pin "2") (pinfunction "S_2") (pintype "passive"))
      (node (ref "R10") (pin "2") (pinfunction "2_2") (pintype "passive"))
      (node (ref "R17") (pin "1") (pinfunction "1_1") (pintype "passive"))
      (node (ref "R18") (pin "1") (pinfunction "1_1") (pintype "passive"))
      (node (ref "R23") (pin "2") (pinfunction "2_2") (pintype "passive"))
      (node (ref "S1") (pin "A2") (pinfunction "1_A2") (pintype "passive"))
      (node (ref "S2") (pin "A2") (pinfunction "1_A2") (pintype "passive"))
      (node (ref "S3") (pin "A2") (pinfunction "1_A2") (pintype "passive"))
      (node (ref "SD1") (pin "6") (pinfunction "VSS_6") (pintype "power_in"))
      (node (ref "SD1") (pin "B") (pinfunction "B_B") (pintype "passive"))
      (node (ref "SD1") (pin "MNT1") (pinfunction "S1_MNT1") (pintype "passive"))
      (node (ref "SD1") (pin "MNT2") (pinfunction "S2_MNT2") (pintype "passive"))
      (node (ref "SD1") (pin "MNT3") (pinfunction "S3_MNT3") (pintype "passive"))
      (node (ref "SD1") (pin "MNT4") (pinfunction "S4_MNT4") (pintype "passive"))
      (node (ref "U$1") (pin "2") (pinfunction "GND_2") (pintype "power_in"))
      (node (ref "U1") (pin "1") (pinfunction "GND_1") (pintype "bidirectional"))
      (node (ref "U1") (pin "15") (pinfunction "GND_15") (pintype "bidirectional"))
      (node (ref "U1") (pin "38") (pinfunction "GND_38") (pintype "bidirectional"))
      (node (ref "U1") (pin "GND") (pinfunction "GND_GND") (pintype "bidirectional"))
      (node (ref "U2") (pin "4") (pinfunction "GND_4") (pintype "passive"))
      (node (ref "USB1") (pin "P5") (pinfunction "GND_P5") (pintype "bidirectional"))
    )
    (net (code "151") (name "Net-(C42-Pad2)") (class "Default")
      (node (ref "C42") (pin "2") (pinfunction "2_2") (pintype "passive"))
      (node (ref "R13") (pin "1") (pinfunction "1_1") (pintype "passive"))
    )
    (net (code "152") (name "Net-(C43-Pad2)") (class "Default")
      (node (ref "C43") (pin "2") (pinfunction "2_2") (pintype "passive"))
      (node (ref "R14") (pin "1") (pinfunction "1_1") (pintype "passive"))
    )
    (net (code "153") (name "Net-(C44-Pad1)") (class "Default")
      (node (ref "C44") (pin "1") (pinfunction "1_1") (pintype "passive"))
      (node (ref "R16") (pin "2") (pinfunction "2_2") (pintype "passive"))
      (node (ref "R18") (pin "2") (pinfunction "2_2") (pintype "passive"))
      (node (ref "R20") (pin "1") (pinfunction "1_1") (pintype "passive"))
    )
    (net (code "154") (name "Net-(IC2-__CLK2)") (class "Default")
      (node (ref "IC2") (pin "24") (pinfunction "__CLK2_24") (pintype "input"))
      (node (ref "U$1") (pin "3") (pinfunction "FO_3") (pintype "output"))
    )
    (net (code "155") (name "Net-(IC2-__IO_77)") (class "Default")
      (node (ref "IC2") (pin "135") (pinfunction "__IO_77_135") (pintype "bidirectional"))
      (node (ref "TP6") (pin "TP") (pinfunction "TP_TP") (pintype "input"))
    )
    (net (code "156") (name "Net-(IC2-__IO_78)") (class "Default")
      (node (ref "IC2") (pin "136") (pinfunction "__IO_78_136") (pintype "bidirectional"))
      (node (ref "TP5") (pin "TP") (pinfunction "TP_TP") (pintype "input"))
    )
    (net (code "157") (name "Net-(IC2-__NSTATUS)") (class "Default")
      (node (ref "IC2") (pin "9") (pinfunction "__NSTATUS_9") (pintype "bidirectional"))
      (node (ref "R6") (pin "1") (pinfunction "1_1") (pintype "passive"))
    )
    (net (code "158") (name "Net-(IC3A-A1)") (class "Default")
      (node (ref "IC3") (pin "2") (pinfunction "A1_2") (pintype "bidirectional"))
      (node (ref "RN1") (pin "8") (pinfunction "2_8") (pintype "passive"))
    )
    (net (code "159") (name "Net-(IC3A-A2)") (class "Default")
      (node (ref "IC3") (pin "3") (pinfunction "A2_3") (pintype "bidirectional"))
      (node (ref "RN1") (pin "7") (pinfunction "2_7") (pintype "passive"))
    )
    (net (code "160") (name "Net-(IC3A-A3)") (class "Default")
      (node (ref "IC3") (pin "4") (pinfunction "A3_4") (pintype "bidirectional"))
      (node (ref "RN1") (pin "6") (pinfunction "2_6") (pintype "passive"))
    )
    (net (code "161") (name "Net-(IC3A-A4)") (class "Default")
      (node (ref "IC3") (pin "5") (pinfunction "A4_5") (pintype "bidirectional"))
      (node (ref "RN1") (pin "5") (pinfunction "2_5") (pintype "passive"))
    )
    (net (code "162") (name "Net-(IC3A-A5)") (class "Default")
      (node (ref "IC3") (pin "6") (pinfunction "A5_6") (pintype "bidirectional"))
      (node (ref "RN2") (pin "8") (pinfunction "2_8") (pintype "passive"))
    )
    (net (code "163") (name "Net-(IC3A-A6)") (class "Default")
      (node (ref "IC3") (pin "7") (pinfunction "A6_7") (pintype "bidirectional"))
      (node (ref "RN2") (pin "7") (pinfunction "2_7") (pintype "passive"))
    )
    (net (code "164") (name "Net-(IC3A-A7)") (class "Default")
      (node (ref "IC3") (pin "8") (pinfunction "A7_8") (pintype "bidirectional"))
      (node (ref "RN2") (pin "6") (pinfunction "2_6") (pintype "passive"))
    )
    (net (code "165") (name "Net-(IC3A-A8)") (class "Default")
      (node (ref "IC3") (pin "9") (pinfunction "A8_9") (pintype "bidirectional"))
      (node (ref "RN2") (pin "5") (pinfunction "2_5") (pintype "passive"))
    )
    (net (code "166") (name "Net-(IC4A-A1)") (class "Default")
      (node (ref "IC4") (pin "2") (pinfunction "A1_2") (pintype "bidirectional"))
      (node (ref "RN7") (pin "8") (pinfunction "2_8") (pintype "passive"))
    )
    (net (code "167") (name "Net-(IC4A-A2)") (class "Default")
      (node (ref "IC4") (pin "3") (pinfunction "A2_3") (pintype "bidirectional"))
      (node (ref "RN7") (pin "7") (pinfunction "2_7") (pintype "passive"))
    )
    (net (code "168") (name "Net-(IC4A-A3)") (class "Default")
      (node (ref "IC4") (pin "4") (pinfunction "A3_4") (pintype "bidirectional"))
      (node (ref "RN7") (pin "6") (pinfunction "2_6") (pintype "passive"))
    )
    (net (code "169") (name "Net-(IC4A-A4)") (class "Default")
      (node (ref "IC4") (pin "5") (pinfunction "A4_5") (pintype "bidirectional"))
      (node (ref "RN7") (pin "5") (pinfunction "2_5") (pintype "passive"))
    )
    (net (code "170") (name "Net-(IC4A-A5)") (class "Default")
      (node (ref "IC4") (pin "6") (pinfunction "A5_6") (pintype "bidirectional"))
      (node (ref "RN8") (pin "8") (pinfunction "2_8") (pintype "passive"))
    )
    (net (code "171") (name "Net-(IC4A-A6)") (class "Default")
      (node (ref "IC4") (pin "7") (pinfunction "A6_7") (pintype "bidirectional"))
      (node (ref "RN8") (pin "7") (pinfunction "2_7") (pintype "passive"))
    )
    (net (code "172") (name "Net-(IC4A-A7)") (class "Default")
      (node (ref "IC4") (pin "8") (pinfunction "A7_8") (pintype "bidirectional"))
      (node (ref "RN8") (pin "6") (pinfunction "2_6") (pintype "passive"))
    )
    (net (code "173") (name "Net-(IC4A-A8)") (class "Default")
      (node (ref "IC4") (pin "9") (pinfunction "A8_9") (pintype "bidirectional"))
      (node (ref "RN8") (pin "5") (pinfunction "2_5") (pintype "passive"))
    )
    (net (code "174") (name "Net-(IC5-BST)") (class "Default")
      (node (ref "IC5") (pin "5") (pinfunction "BST_5") (pintype "passive"))
      (node (ref "R13") (pin "2") (pinfunction "2_2") (pintype "passive"))
    )
    (net (code "175") (name "Net-(IC5-EN)") (class "Default")
      (node (ref "IC5") (pin "6") (pinfunction "EN_6") (pintype "input"))
      (node (ref "R11") (pin "1") (pinfunction "1_1") (pintype "passive"))
    )
    (net (code "176") (name "Net-(IC5-FB)") (class "Default")
      (node (ref "IC5") (pin "8") (pinfunction "FB_8") (pintype "passive"))
      (node (ref "R15") (pin "1") (pinfunction "1_1") (pintype "passive"))
    )
    (net (code "177") (name "Net-(IC5-SS)") (class "Default")
      (node (ref "C38") (pin "2") (pinfunction "2_2") (pintype "passive"))
      (node (ref "IC5") (pin "1") (pinfunction "SS_1") (pintype "passive"))
    )
    (net (code "178") (name "Net-(IC5-VCC)") (class "Default")
      (node (ref "C35") (pin "2") (pinfunction "2_2") (pintype "passive"))
      (node (ref "IC5") (pin "7") (pinfunction "VCC_7") (pintype "passive"))
    )
    (net (code "179") (name "Net-(IC6-BST)") (class "Default")
      (node (ref "IC6") (pin "5") (pinfunction "BST_5") (pintype "passive"))
      (node (ref "R14") (pin "2") (pinfunction "2_2") (pintype "passive"))
    )
    (net (code "180") (name "Net-(IC6-EN)") (class "Default")
      (node (ref "IC6") (pin "6") (pinfunction "EN_6") (pintype "input"))
      (node (ref "R12") (pin "1") (pinfunction "1_1") (pintype "passive"))
    )
    (net (code "181") (name "Net-(IC6-FB)") (class "Default")
      (node (ref "IC6") (pin "8") (pinfunction "FB_8") (pintype "passive"))
      (node (ref "R16") (pin "1") (pinfunction "1_1") (pintype "passive"))
    )
    (net (code "182") (name "Net-(IC6-SS)") (class "Default")
      (node (ref "C39") (pin "2") (pinfunction "2_2") (pintype "passive"))
      (node (ref "IC6") (pin "1") (pinfunction "SS_1") (pintype "passive"))
    )
    (net (code "183") (name "Net-(IC6-VCC)") (class "Default")
      (node (ref "C36") (pin "2") (pinfunction "2_2") (pintype "passive"))
      (node (ref "IC6") (pin "7") (pinfunction "VCC_7") (pintype "passive"))
    )
    (net (code "184") (name "Net-(IC7-DM)") (class "Default")
      (node (ref "IC7") (pin "2") (pinfunction "DM_2") (pintype "passive"))
      (node (ref "USB1") (pin "P2") (pinfunction "D-_P2") (pintype "bidirectional"))
    )
    (net (code "185") (name "Net-(IC7-DP)") (class "Default")
      (node (ref "IC7") (pin "1") (pinfunction "DP_1") (pintype "passive"))
      (node (ref "USB1") (pin "P3") (pinfunction "D+_P3") (pintype "bidirectional"))
    )
    (net (code "186") (name "Net-(IC10A-A1)") (class "Default")
      (node (ref "IC10") (pin "2") (pinfunction "A1_2") (pintype "bidirectional"))
      (node (ref "RN3") (pin "8") (pinfunction "2_8") (pintype "passive"))
    )
    (net (code "187") (name "Net-(IC10A-A2)") (class "Default")
      (node (ref "IC10") (pin "3") (pinfunction "A2_3") (pintype "bidirectional"))
      (node (ref "RN3") (pin "7") (pinfunction "2_7") (pintype "passive"))
    )
    (net (code "188") (name "Net-(IC10A-A3)") (class "Default")
      (node (ref "IC10") (pin "4") (pinfunction "A3_4") (pintype "bidirectional"))
      (node (ref "RN3") (pin "6") (pinfunction "2_6") (pintype "passive"))
    )
    (net (code "189") (name "Net-(IC10A-A4)") (class "Default")
      (node (ref "IC10") (pin "5") (pinfunction "A4_5") (pintype "bidirectional"))
      (node (ref "RN3") (pin "5") (pinfunction "2_5") (pintype "passive"))
    )
    (net (code "190") (name "Net-(IC10A-A5)") (class "Default")
      (node (ref "IC10") (pin "6") (pinfunction "A5_6") (pintype "bidirectional"))
      (node (ref "RN4") (pin "8") (pinfunction "2_8") (pintype "passive"))
    )
    (net (code "191") (name "Net-(IC10A-A6)") (class "Default")
      (node (ref "IC10") (pin "7") (pinfunction "A6_7") (pintype "bidirectional"))
      (node (ref "RN4") (pin "7") (pinfunction "2_7") (pintype "passive"))
    )
    (net (code "192") (name "Net-(IC10A-A7)") (class "Default")
      (node (ref "IC10") (pin "8") (pinfunction "A7_8") (pintype "bidirectional"))
      (node (ref "RN4") (pin "6") (pinfunction "2_6") (pintype "passive"))
    )
    (net (code "193") (name "Net-(IC10A-A8)") (class "Default")
      (node (ref "IC10") (pin "9") (pinfunction "A8_9") (pintype "bidirectional"))
      (node (ref "RN4") (pin "5") (pinfunction "2_5") (pintype "passive"))
    )
    (net (code "194") (name "Net-(IC11A-A1)") (class "Default")
      (node (ref "IC11") (pin "2") (pinfunction "A1_2") (pintype "bidirectional"))
      (node (ref "RN5") (pin "8") (pinfunction "2_8") (pintype "passive"))
    )
    (net (code "195") (name "Net-(IC11A-A2)") (class "Default")
      (node (ref "IC11") (pin "3") (pinfunction "A2_3") (pintype "bidirectional"))
      (node (ref "RN5") (pin "7") (pinfunction "2_7") (pintype "passive"))
    )
    (net (code "196") (name "Net-(IC11A-A3)") (class "Default")
      (node (ref "IC11") (pin "4") (pinfunction "A3_4") (pintype "bidirectional"))
      (node (ref "RN5") (pin "6") (pinfunction "2_6") (pintype "passive"))
    )
    (net (code "197") (name "Net-(IC11A-A4)") (class "Default")
      (node (ref "IC11") (pin "5") (pinfunction "A4_5") (pintype "bidirectional"))
      (node (ref "RN5") (pin "5") (pinfunction "2_5") (pintype "passive"))
    )
    (net (code "198") (name "Net-(IC11A-A5)") (class "Default")
      (node (ref "IC11") (pin "6") (pinfunction "A5_6") (pintype "bidirectional"))
      (node (ref "RN6") (pin "8") (pinfunction "2_8") (pintype "passive"))
    )
    (net (code "199") (name "Net-(IC11A-A6)") (class "Default")
      (node (ref "IC11") (pin "7") (pinfunction "A6_7") (pintype "bidirectional"))
      (node (ref "RN6") (pin "7") (pinfunction "2_7") (pintype "passive"))
    )
    (net (code "200") (name "Net-(IC11A-A7)") (class "Default")
      (node (ref "IC11") (pin "8") (pinfunction "A7_8") (pintype "bidirectional"))
      (node (ref "RN6") (pin "6") (pinfunction "2_6") (pintype "passive"))
    )
    (net (code "201") (name "Net-(IC11A-A8)") (class "Default")
      (node (ref "IC11") (pin "9") (pinfunction "A8_9") (pintype "bidirectional"))
      (node (ref "RN6") (pin "5") (pinfunction "2_5") (pintype "passive"))
    )
    (net (code "202") (name "Net-(LED1-PadC)") (class "Default")
      (node (ref "LED1") (pin "C") (pinfunction "C_C") (pintype "passive"))
      (node (ref "R21") (pin "1") (pinfunction "1_1") (pintype "passive"))
    )
    (net (code "203") (name "Net-(LED2-PadC)") (class "Default")
      (node (ref "LED2") (pin "C") (pinfunction "C_C") (pintype "passive"))
      (node (ref "R22") (pin "1") (pinfunction "1_1") (pintype "passive"))
    )
    (net (code "204") (name "Net-(LED3-PadC)") (class "Default")
      (node (ref "LED3") (pin "C") (pinfunction "C_C") (pintype "passive"))
      (node (ref "R23") (pin "1") (pinfunction "1_1") (pintype "passive"))
    )
    (net (code "205") (name "Net-(R15-Pad2)") (class "Default")
      (node (ref "R15") (pin "2") (pinfunction "2_2") (pintype "passive"))
      (node (ref "R17") (pin "2") (pinfunction "2_2") (pintype "passive"))
      (node (ref "R19") (pin "1") (pinfunction "1_1") (pintype "passive"))
    )
    (net (code "206") (name "unconnected-(CONN1-BUSACK-PadA26)") (class "Default")
      (node (ref "CONN1") (pin "A26") (pinfunction "BUSACK_A26") (pintype "bidirectional"))
    )
    (net (code "207") (name "unconnected-(CONN1-BUSREQ-PadA19)") (class "Default")
      (node (ref "CONN1") (pin "A19") (pinfunction "BUSREQ_A19") (pintype "bidirectional"))
    )
    (net (code "208") (name "unconnected-(CONN1-HALT-PadB15)") (class "Default")
      (node (ref "CONN1") (pin "B15") (pinfunction "HALT_B15") (pintype "bidirectional"))
    )
    (net (code "209") (name "unconnected-(CONN1-IORQULA-PadA13)") (class "Default")
      (node (ref "CONN1") (pin "A13") (pinfunction "IORQULA_A13") (pintype "bidirectional"))
    )
    (net (code "210") (name "unconnected-(CONN1-NC-PadB28)") (class "Default")
      (node (ref "CONN1") (pin "B28") (pinfunction "NC_B28") (pintype "bidirectional"))
    )
    (net (code "211") (name "unconnected-(CONN1-NC3-PadB4)") (class "Default")
      (node (ref "CONN1") (pin "B4") (pinfunction "NC3_B4") (pintype "passive"))
    )
    (net (code "212") (name "unconnected-(CONN1-NMI-PadB14)") (class "Default")
      (node (ref "CONN1") (pin "B14") (pinfunction "NMI_B14") (pintype "bidirectional"))
    )
    (net (code "213") (name "unconnected-(CONN1-U-PadA18)") (class "Default")
      (node (ref "CONN1") (pin "A18") (pinfunction "U_A18") (pintype "bidirectional"))
    )
    (net (code "214") (name "unconnected-(CONN1-V-PadA17)") (class "Default")
      (node (ref "CONN1") (pin "A17") (pinfunction "V_A17") (pintype "bidirectional"))
    )
    (net (code "215") (name "unconnected-(CONN1-VIDEO-PadA15)") (class "Default")
      (node (ref "CONN1") (pin "A15") (pinfunction "VIDEO_A15") (pintype "bidirectional"))
    )
    (net (code "216") (name "unconnected-(CONN1-WAIT-PadB21)") (class "Default")
      (node (ref "CONN1") (pin "B21") (pinfunction "WAIT_B21") (pintype "bidirectional"))
    )
    (net (code "217") (name "unconnected-(CONN1-YL-PadA16)") (class "Default")
      (node (ref "CONN1") (pin "A16") (pinfunction "YL_A16") (pintype "bidirectional"))
    )
    (net (code "218") (name "unconnected-(CONN2-Pad6)") (class "Default")
      (node (ref "CONN2") (pin "6") (pinfunction "6_6") (pintype "passive"))
    )
    (net (code "219") (name "unconnected-(CONN2-Pad7)") (class "Default")
      (node (ref "CONN2") (pin "7") (pinfunction "7_7") (pintype "passive"))
    )
    (net (code "220") (name "unconnected-(CONN2-Pad8)") (class "Default")
      (node (ref "CONN2") (pin "8") (pinfunction "8_8") (pintype "passive"))
    )
    (net (code "221") (name "unconnected-(IC2-__CLK3-Pad25)") (class "Default")
      (node (ref "IC2") (pin "25") (pinfunction "__CLK3_25") (pintype "input"))
    )
    (net (code "222") (name "unconnected-(IC2-__CLK4-Pad91)") (class "Default")
      (node (ref "IC2") (pin "91") (pinfunction "__CLK4_91") (pintype "input"))
    )
    (net (code "223") (name "unconnected-(IC2-__CLK5-Pad90)") (class "Default")
      (node (ref "IC2") (pin "90") (pinfunction "__CLK5_90") (pintype "input"))
    )
    (net (code "224") (name "unconnected-(IC2-__CLK6-Pad89)") (class "Default")
      (node (ref "IC2") (pin "89") (pinfunction "__CLK6_89") (pintype "input"))
    )
    (net (code "225") (name "unconnected-(IC2-__CLK7-Pad88)") (class "Default")
      (node (ref "IC2") (pin "88") (pinfunction "__CLK7_88") (pintype "input"))
    )
    (net (code "226") (name "unconnected-(IC2-__IO_76-Pad133)") (class "Default")
      (node (ref "IC2") (pin "133") (pinfunction "__IO_76_133") (pintype "bidirectional"))
    )
    (net (code "227") (name "unconnected-(IC7-RTS-Pad4)") (class "Default")
      (node (ref "IC7") (pin "4") (pinfunction "RTS_4") (pintype "output"))
    )
    (net (code "228") (name "unconnected-(IC9A-DQ8-Pad42)") (class "Default")
      (node (ref "IC9") (pin "42") (pinfunction "DQ8_42") (pintype "tri_state"))
    )
    (net (code "229") (name "unconnected-(IC9A-DQ9-Pad44)") (class "Default")
      (node (ref "IC9") (pin "44") (pinfunction "DQ9_44") (pintype "tri_state"))
    )
    (net (code "230") (name "unconnected-(IC9A-DQ10-Pad45)") (class "Default")
      (node (ref "IC9") (pin "45") (pinfunction "DQ10_45") (pintype "tri_state"))
    )
    (net (code "231") (name "unconnected-(IC9A-DQ11-Pad47)") (class "Default")
      (node (ref "IC9") (pin "47") (pinfunction "DQ11_47") (pintype "tri_state"))
    )
    (net (code "232") (name "unconnected-(IC9A-DQ12-Pad48)") (class "Default")
      (node (ref "IC9") (pin "48") (pinfunction "DQ12_48") (pintype "tri_state"))
    )
    (net (code "233") (name "unconnected-(IC9A-DQ13-Pad50)") (class "Default")
      (node (ref "IC9") (pin "50") (pinfunction "DQ13_50") (pintype "tri_state"))
    )
    (net (code "234") (name "unconnected-(IC9A-DQ14-Pad51)") (class "Default")
      (node (ref "IC9") (pin "51") (pinfunction "DQ14_51") (pintype "tri_state"))
    )
    (net (code "235") (name "unconnected-(IC9A-DQ15-Pad53)") (class "Default")
      (node (ref "IC9") (pin "53") (pinfunction "DQ15_53") (pintype "tri_state"))
    )
    (net (code "236") (name "unconnected-(IC9A-DQML-Pad15)") (class "Default")
      (node (ref "IC9") (pin "15") (pinfunction "DQML_15") (pintype "input"))
    )
    (net (code "237") (name "unconnected-(IC9A-NC-Pad40)") (class "Default")
      (node (ref "IC9") (pin "40") (pinfunction "NC_40") (pintype "no_connect"))
    )
    (net (code "238") (name "unconnected-(U1-IO2-Pad24)") (class "Default")
      (node (ref "U1") (pin "24") (pinfunction "IO2_24") (pintype "bidirectional"))
    )
    (net (code "239") (name "unconnected-(U1-IO4-Pad26)") (class "Default")
      (node (ref "U1") (pin "26") (pinfunction "IO4_26") (pintype "bidirectional"))
    )
    (net (code "240") (name "unconnected-(U1-IO12-Pad14)") (class "Default")
      (node (ref "U1") (pin "14") (pinfunction "IO12_14") (pintype "bidirectional"))
    )
    (net (code "241") (name "unconnected-(U1-IO13-Pad16)") (class "Default")
      (node (ref "U1") (pin "16") (pinfunction "IO13_16") (pintype "bidirectional"))
    )
    (net (code "242") (name "unconnected-(U1-IO16-Pad27)") (class "Default")
      (node (ref "U1") (pin "27") (pinfunction "IO16_27") (pintype "bidirectional"))
    )
    (net (code "243") (name "unconnected-(U1-IO17-Pad28)") (class "Default")
      (node (ref "U1") (pin "28") (pinfunction "IO17_28") (pintype "bidirectional"))
    )
    (net (code "244") (name "unconnected-(U1-IO35-Pad7)") (class "Default")
      (node (ref "U1") (pin "7") (pinfunction "IO35_7") (pintype "input"))
    )
    (net (code "245") (name "unconnected-(U1-NC-Pad32)") (class "Default")
      (node (ref "U1") (pin "32") (pinfunction "NC_32") (pintype "bidirectional"))
    )
    (net (code "246") (name "unconnected-(U1-SENSOR_VN-Pad5)") (class "Default")
      (node (ref "U1") (pin "5") (pinfunction "SENSOR_VN_5") (pintype "input"))
    )
    (net (code "247") (name "unconnected-(U1-SENSOR_VP-Pad4)") (class "Default")
      (node (ref "U1") (pin "4") (pinfunction "SENSOR_VP_4") (pintype "input"))
    )
    (net (code "248") (name "unconnected-(USB1B-USBID-PadP4)") (class "Default")
      (node (ref "USB1") (pin "P4") (pinfunction "USBID_P4") (pintype "bidirectional"))
    )
    (net (code "249") (name "unconnected-(USB1B-VUSB-PadP1)") (class "Default")
      (node (ref "USB1") (pin "P1") (pinfunction "VUSB_P1") (pintype "bidirectional"))
    )
  )
)
